# TP-34.net
KiCad netlist of a schematic drawn in EAGLE
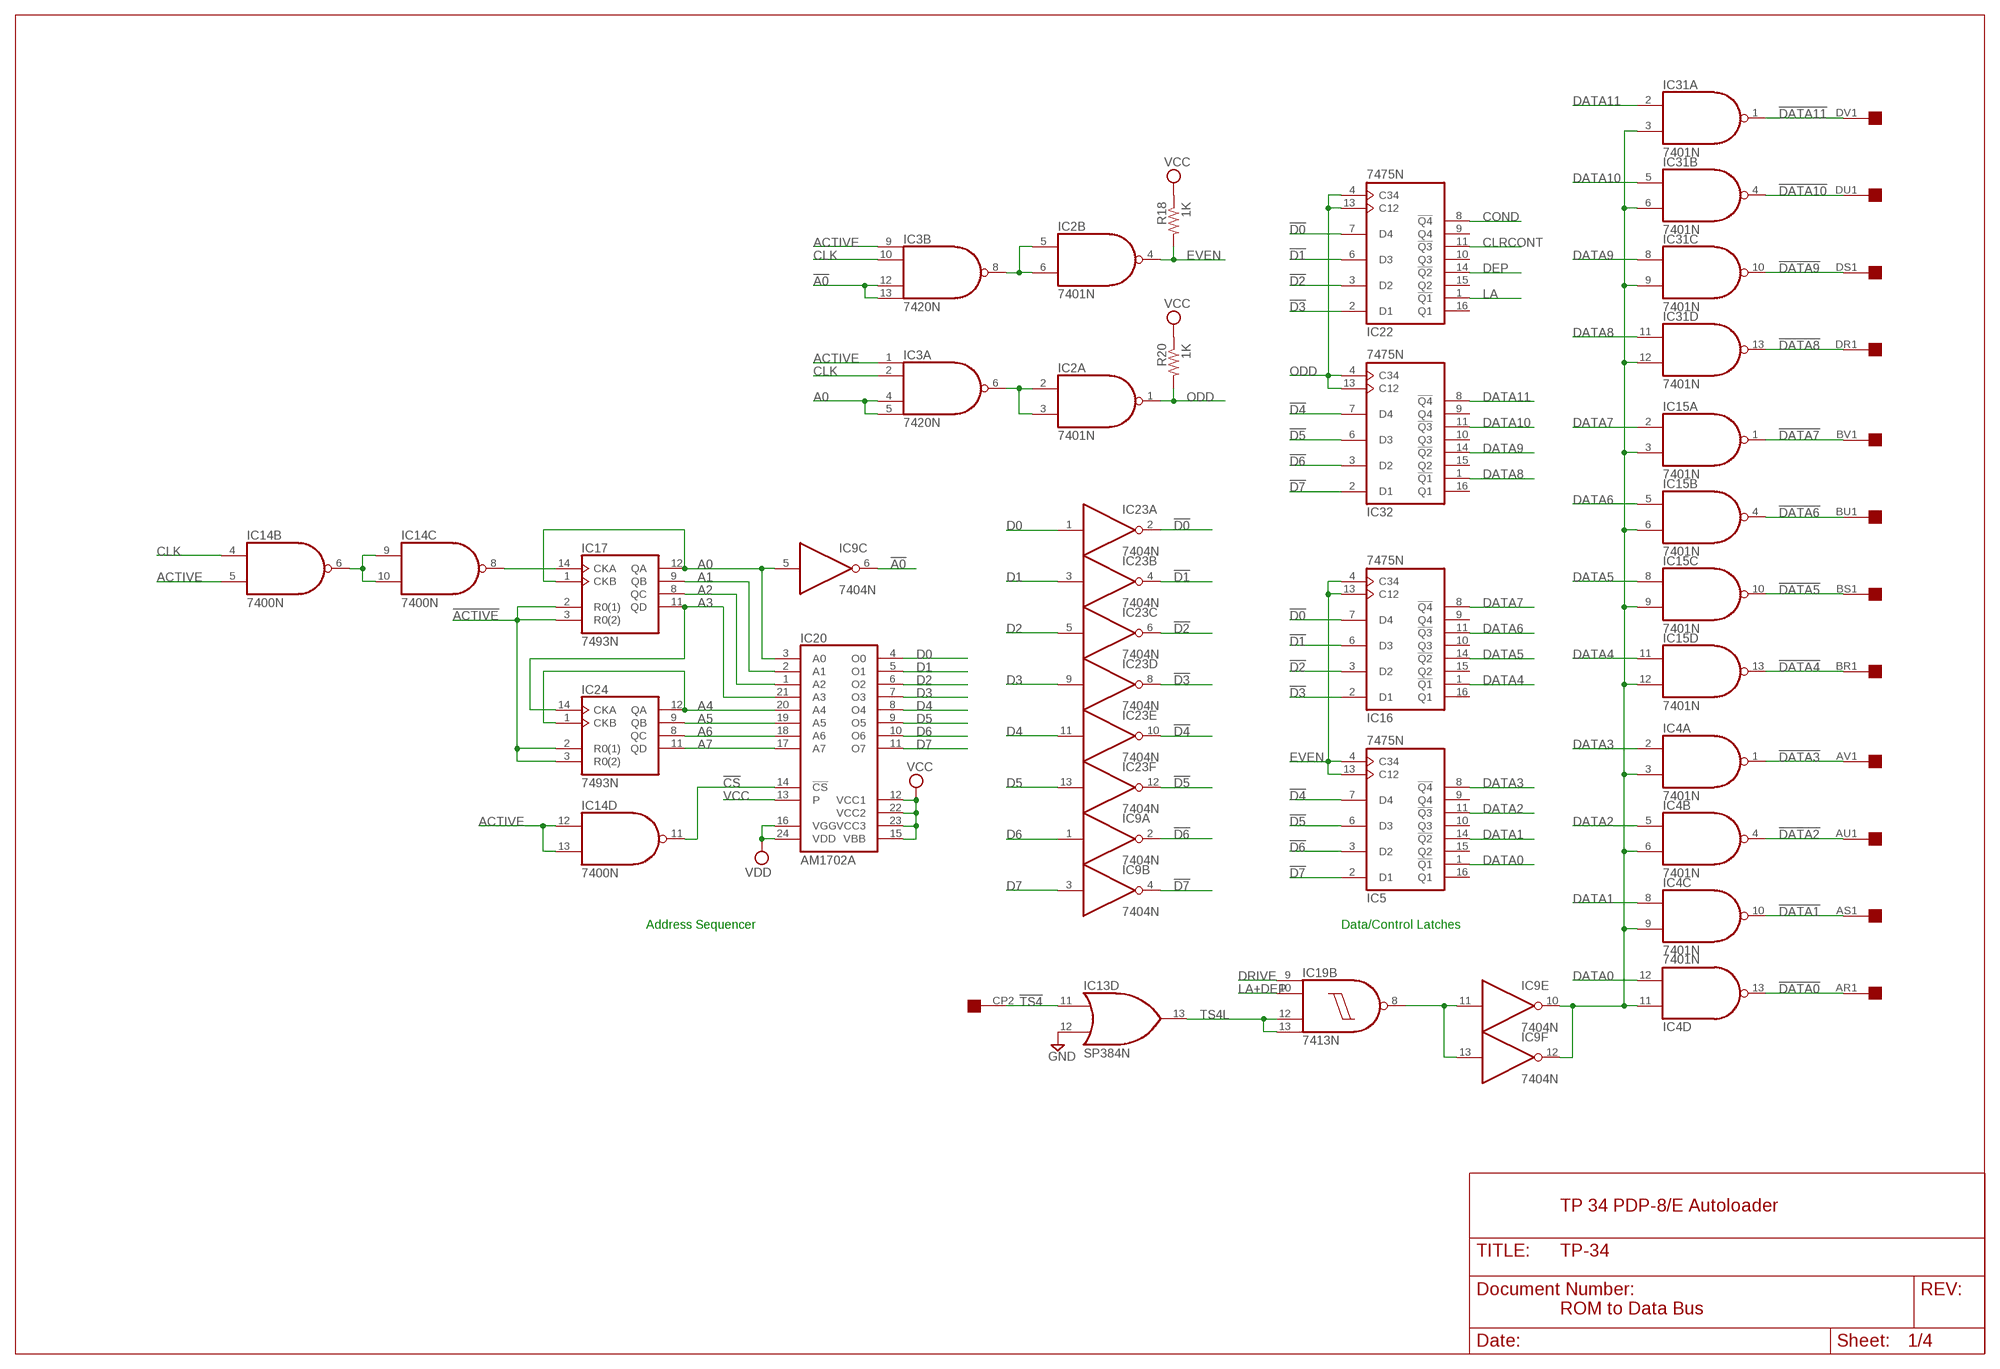
[diagram p0: schematic, sheet 1]
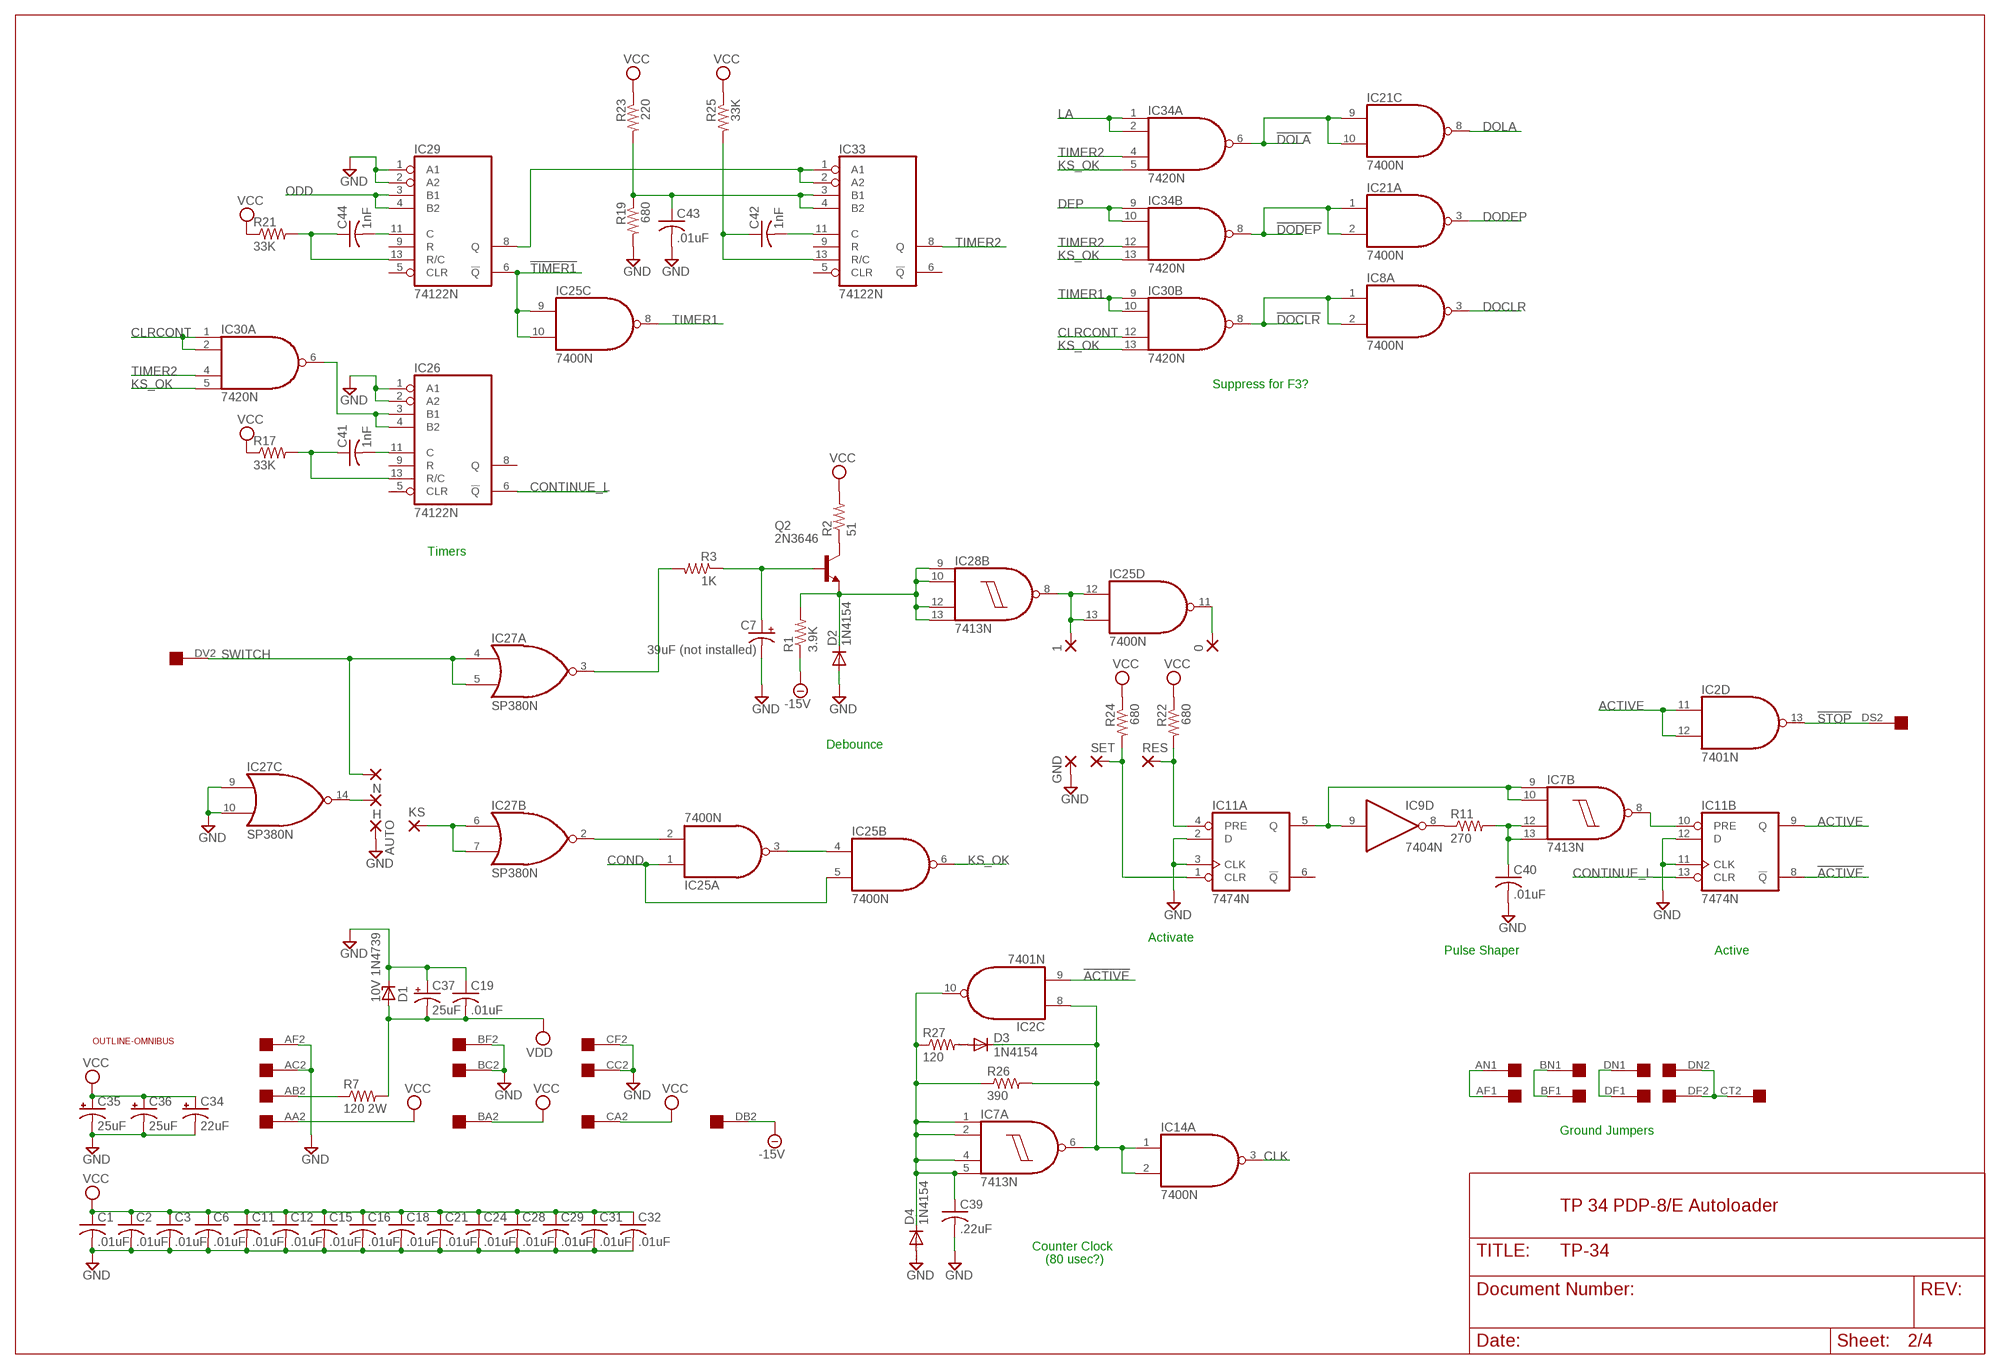
[diagram p1: schematic, sheet 2]
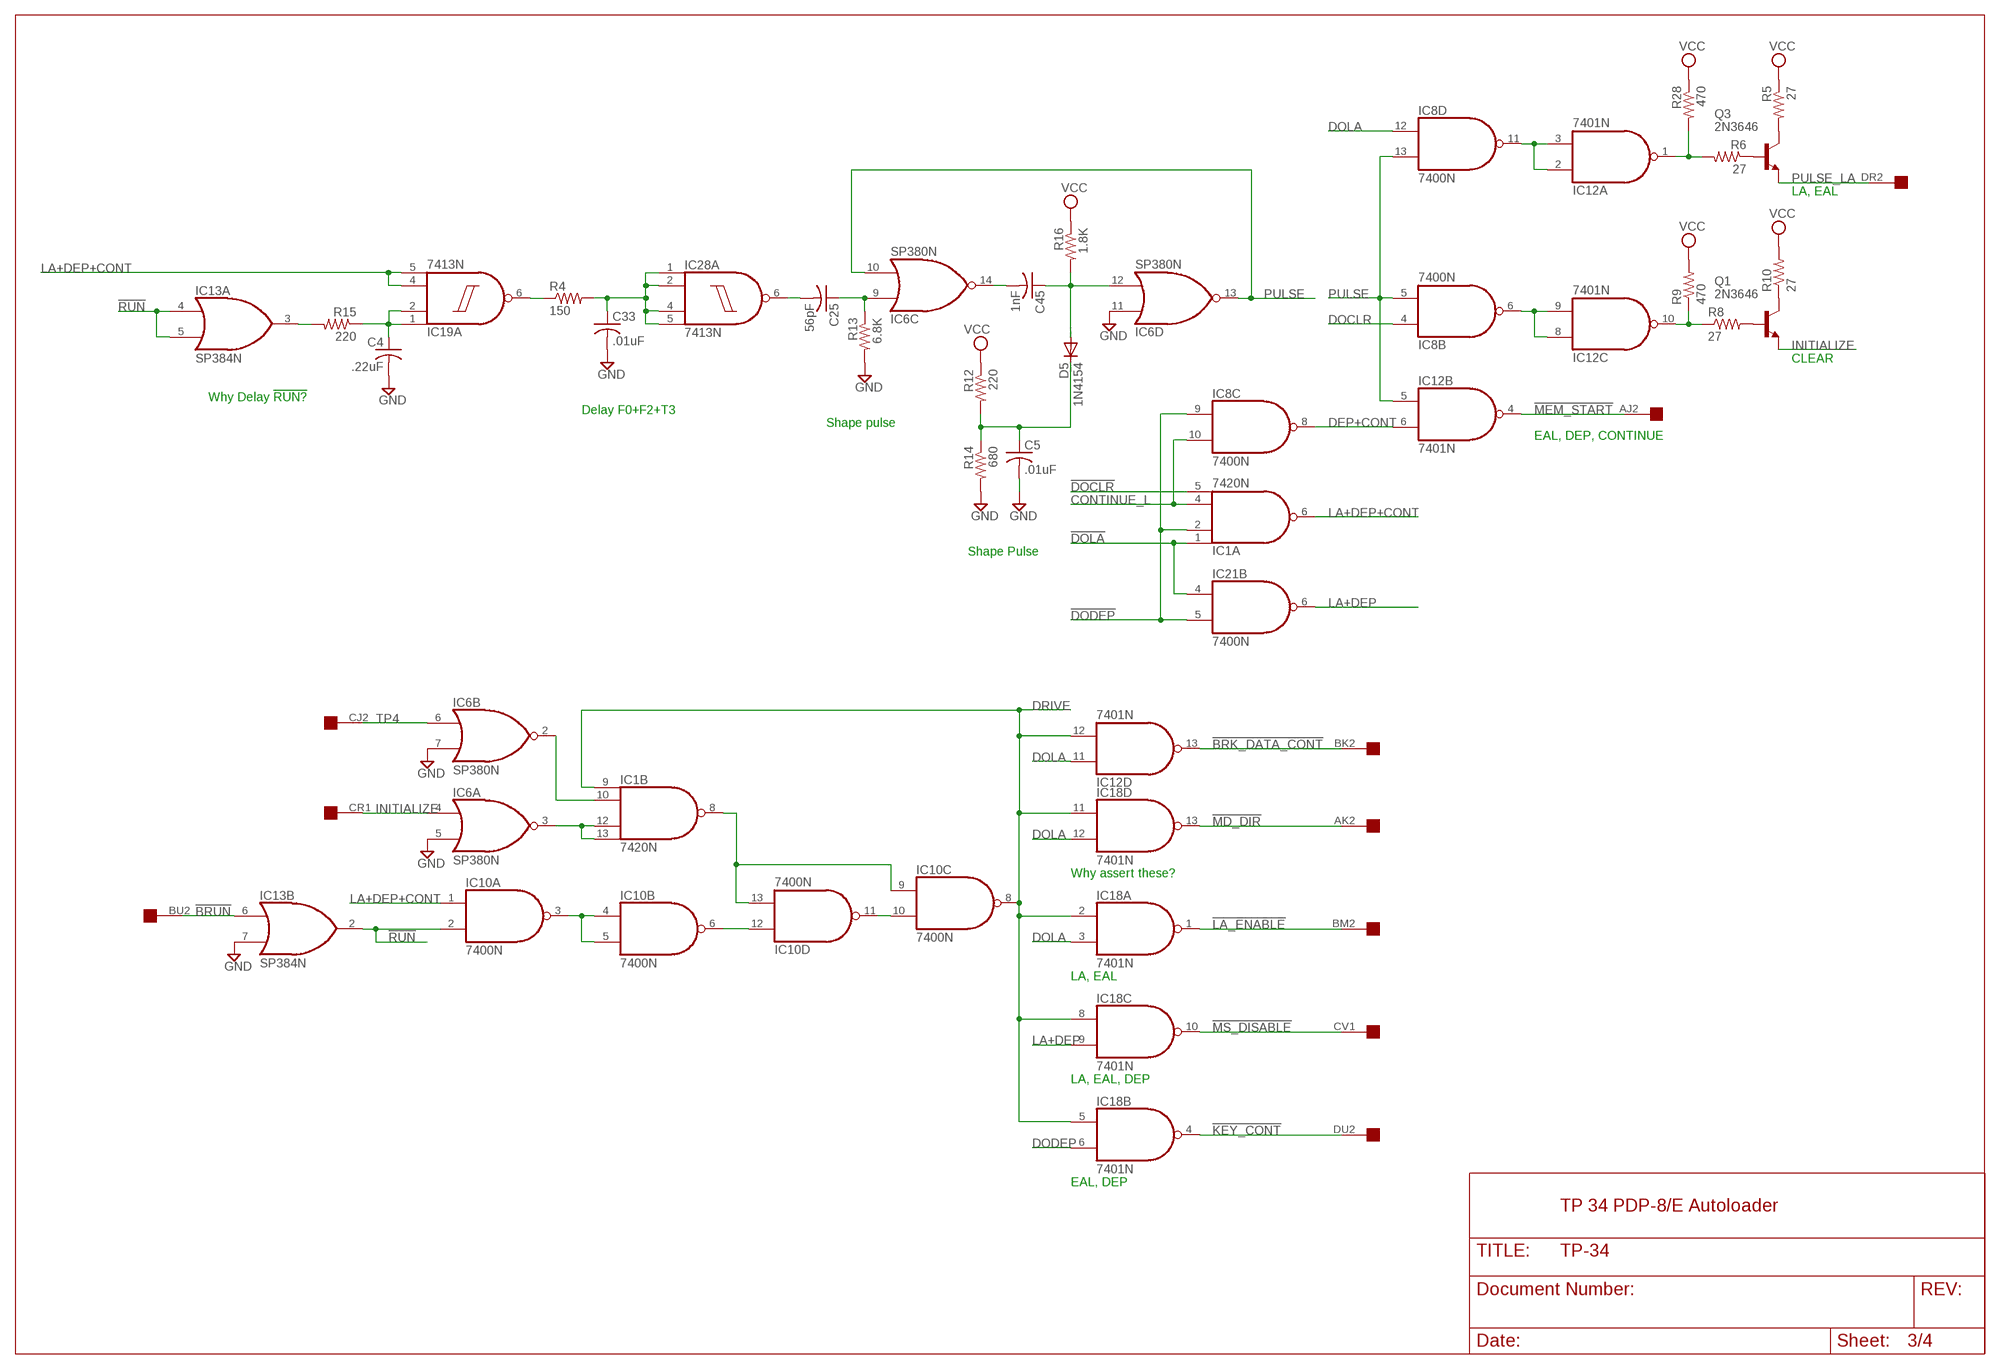
[diagram p2: schematic, sheet 3]
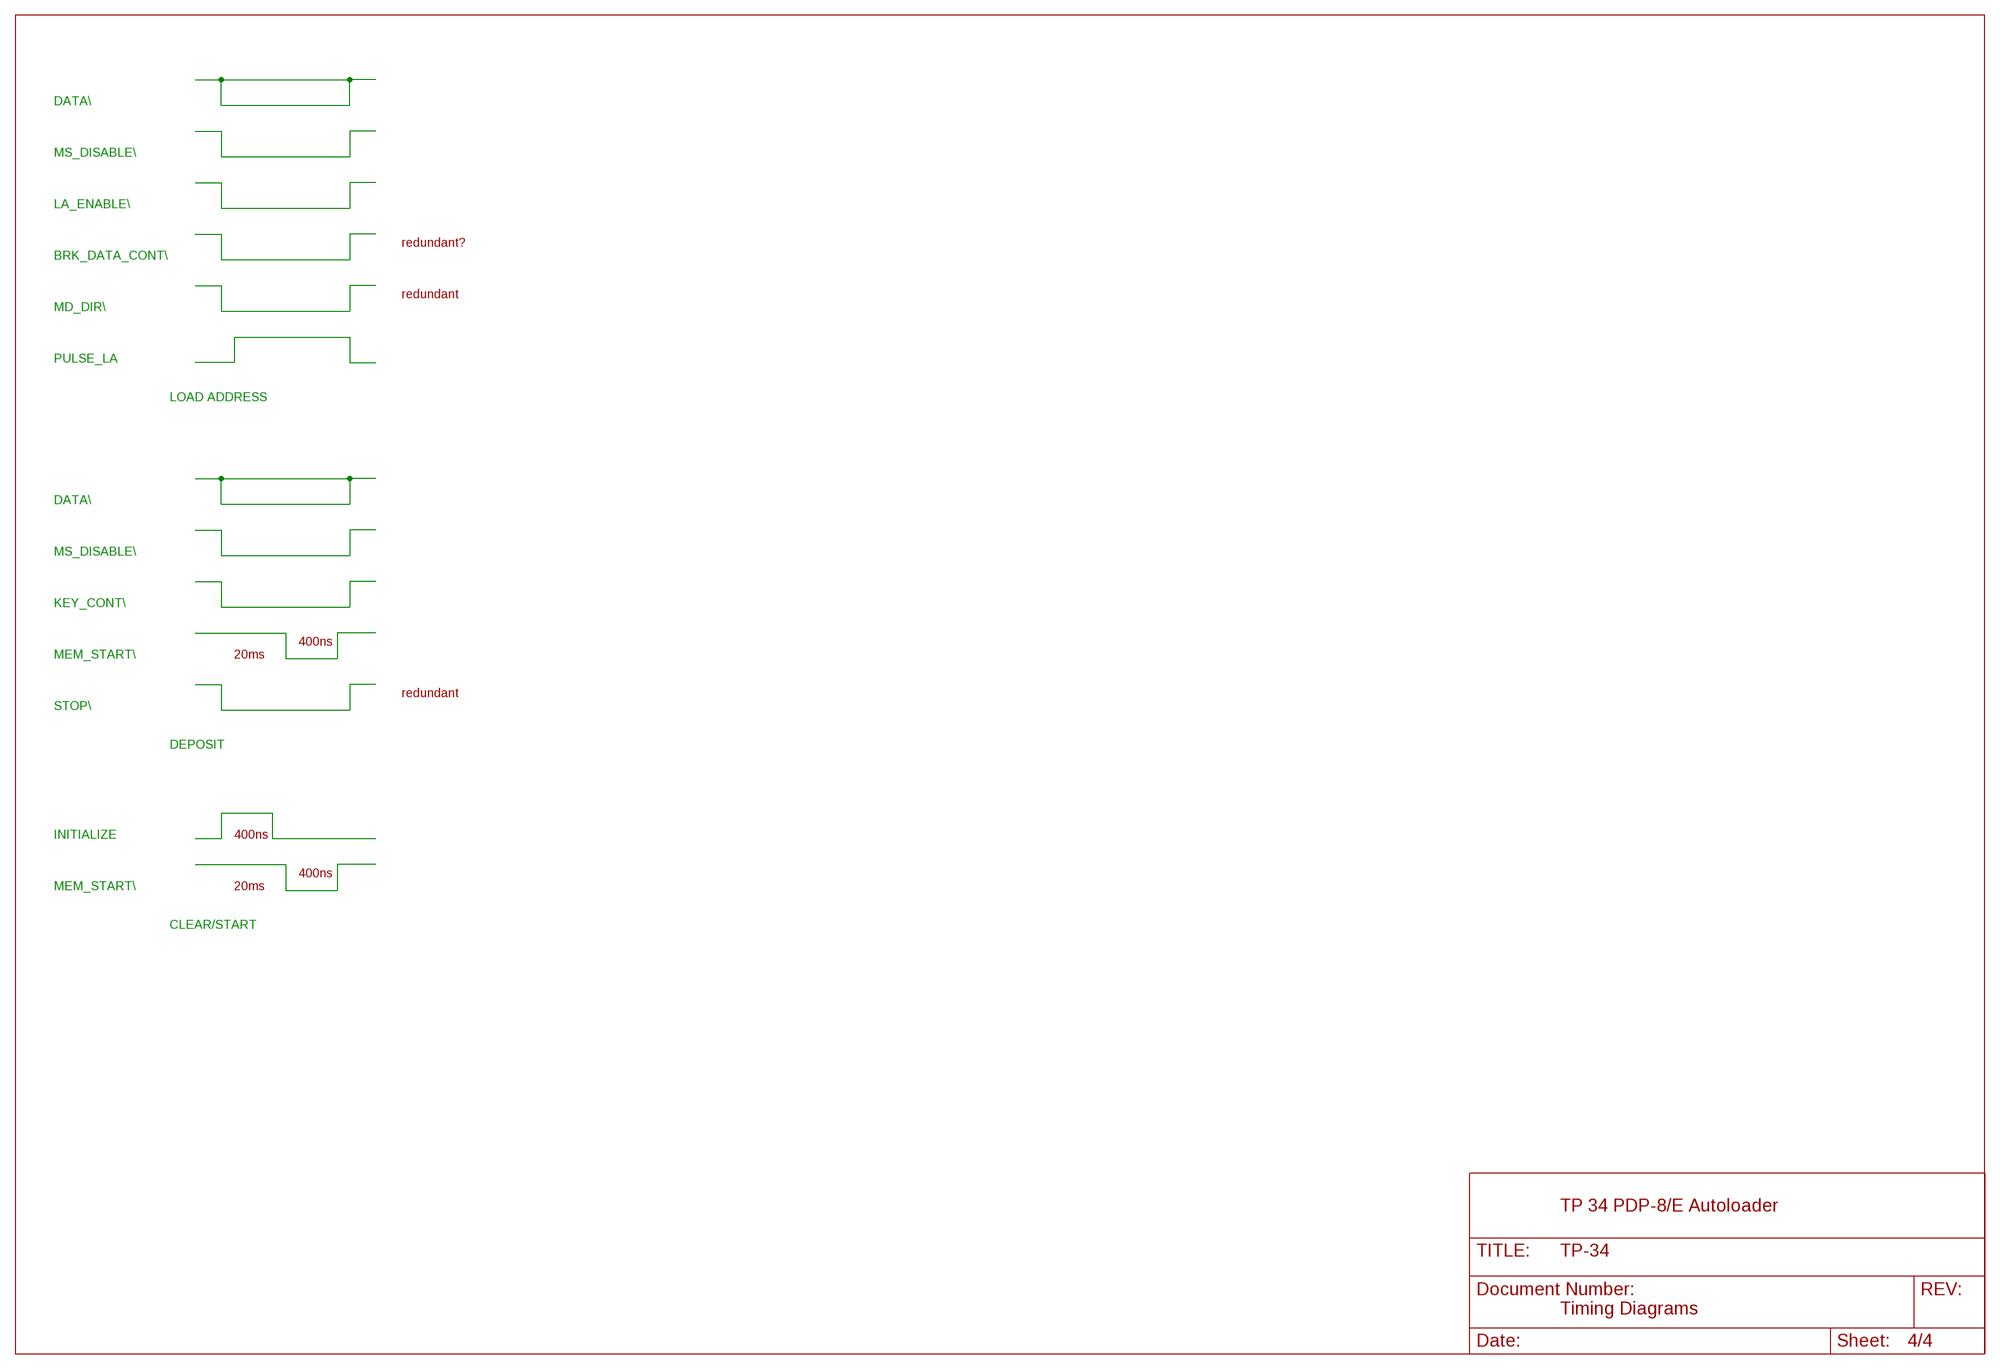
[diagram p3: schematic, sheet 4]

(export (version "E")
  (design (tool "Eeschema 10.0.6"))
  (components
    (comp (ref "0")
      (value "1,6/0,8")
      (footprint "eagle-import:1,6_0,8")
      (libsource (lib "eagle-import") (part "1,6/0,8"))
    )
    (comp (ref "1")
      (value "1,6/0,8")
      (footprint "eagle-import:1,6_0,8")
      (libsource (lib "eagle-import") (part "1,6/0,8"))
    )
    (comp (ref "AUTO")
      (value "1,6/0,8")
      (footprint "eagle-import:1,6_0,8")
      (libsource (lib "eagle-import") (part "1,6/0,8"))
    )
    (comp (ref "C1")
      (value ".01uF")
      (footprint "eagle-import:C075-032X103")
      (libsource (lib "eagle-import") (part "C-US075-032X103"))
    )
    (comp (ref "C2")
      (value ".01uF")
      (footprint "eagle-import:C075-032X103")
      (libsource (lib "eagle-import") (part "C-US075-032X103"))
    )
    (comp (ref "C3")
      (value ".01uF")
      (footprint "eagle-import:C075-032X103")
      (libsource (lib "eagle-import") (part "C-US075-032X103"))
    )
    (comp (ref "C6")
      (value ".01uF")
      (footprint "eagle-import:C075-032X103")
      (libsource (lib "eagle-import") (part "C-US075-032X103"))
    )
    (comp (ref "C7")
      (value "39uF (not installed)")
      (footprint "eagle-import:E15-5")
      (libsource (lib "eagle-import") (part "CPOL-USE15-5AXIAL"))
    )
    (comp (ref "C11")
      (value ".01uF")
      (footprint "eagle-import:C075-032X103")
      (libsource (lib "eagle-import") (part "C-US075-032X103"))
    )
    (comp (ref "C12")
      (value ".01uF")
      (footprint "eagle-import:C075-032X103")
      (libsource (lib "eagle-import") (part "C-US075-032X103"))
    )
    (comp (ref "C15")
      (value ".01uF")
      (footprint "eagle-import:C075-032X103")
      (libsource (lib "eagle-import") (part "C-US075-032X103"))
    )
    (comp (ref "C16")
      (value ".01uF")
      (footprint "eagle-import:C075-032X103")
      (libsource (lib "eagle-import") (part "C-US075-032X103"))
    )
    (comp (ref "C18")
      (value ".01uF")
      (footprint "eagle-import:C075-032X103")
      (libsource (lib "eagle-import") (part "C-US075-032X103"))
    )
    (comp (ref "C19")
      (value ".01uF")
      (footprint "eagle-import:C075-032X103")
      (libsource (lib "eagle-import") (part "C-US075-032X103"))
    )
    (comp (ref "C21")
      (value ".01uF")
      (footprint "eagle-import:C075-032X103")
      (libsource (lib "eagle-import") (part "C-US075-032X103"))
    )
    (comp (ref "C24")
      (value ".01uF")
      (footprint "eagle-import:C075-032X103")
      (libsource (lib "eagle-import") (part "C-US075-032X103"))
    )
    (comp (ref "C28")
      (value ".01uF")
      (footprint "eagle-import:C075-032X103")
      (libsource (lib "eagle-import") (part "C-US075-032X103"))
    )
    (comp (ref "C29")
      (value ".01uF")
      (footprint "eagle-import:C075-032X103")
      (libsource (lib "eagle-import") (part "C-US075-032X103"))
    )
    (comp (ref "C31")
      (value ".01uF")
      (footprint "eagle-import:C075-032X103")
      (libsource (lib "eagle-import") (part "C-US075-032X103"))
    )
    (comp (ref "C32")
      (value ".01uF")
      (footprint "eagle-import:C075-032X103")
      (libsource (lib "eagle-import") (part "C-US075-032X103"))
    )
    (comp (ref "C34")
      (value "22uF")
      (footprint "eagle-import:E12-8")
      (libsource (lib "eagle-import") (part "CPOL-USE20-8AXIAL"))
    )
    (comp (ref "C35")
      (value "25uF")
      (footprint "eagle-import:E15-5")
      (libsource (lib "eagle-import") (part "CPOL-USE15-5AXIAL"))
    )
    (comp (ref "C36")
      (value "25uF")
      (footprint "eagle-import:E15-5")
      (libsource (lib "eagle-import") (part "CPOL-USE15-5AXIAL"))
    )
    (comp (ref "C37")
      (value "25uF")
      (footprint "eagle-import:E15-5")
      (libsource (lib "eagle-import") (part "CPOL-USE15-5AXIAL"))
    )
    (comp (ref "C39")
      (value ".22uF")
      (footprint "eagle-import:C075-032X103")
      (libsource (lib "eagle-import") (part "C-US075-032X103"))
    )
    (comp (ref "C40")
      (value ".01uF")
      (footprint "eagle-import:C075-032X103")
      (libsource (lib "eagle-import") (part "C-US075-032X103"))
    )
    (comp (ref "C41")
      (value "1nF")
      (footprint "eagle-import:C075-032X103")
      (libsource (lib "eagle-import") (part "C-US075-032X103"))
    )
    (comp (ref "C42")
      (value "1nF")
      (footprint "eagle-import:C075-032X103")
      (libsource (lib "eagle-import") (part "C-US075-032X103"))
    )
    (comp (ref "C43")
      (value ".01uF")
      (footprint "eagle-import:C075-032X103")
      (libsource (lib "eagle-import") (part "C-US075-032X103"))
    )
    (comp (ref "C44")
      (value "1nF")
      (footprint "eagle-import:C075-032X103")
      (libsource (lib "eagle-import") (part "C-US075-032X103"))
    )
    (comp (ref "D1")
      (value "10V 1N4739")
      (footprint "eagle-import:C1702-15")
      (libsource (lib "eagle-import") (part "ZENER-DIODEC1702-15"))
    )
    (comp (ref "D2")
      (value "1N4154")
      (footprint "eagle-import:DO35-10")
      (libsource (lib "eagle-import") (part "1N4148DO35-10"))
    )
    (comp (ref "D3")
      (value "1N4154")
      (footprint "eagle-import:DO35-10")
      (libsource (lib "eagle-import") (part "1N4148DO35-10"))
    )
    (comp (ref "D4")
      (value "1N4154")
      (footprint "eagle-import:DO35-10")
      (libsource (lib "eagle-import") (part "1N4148DO35-10"))
    )
    (comp (ref "GND")
      (value "1,6/0,8")
      (footprint "eagle-import:1,6_0,8")
      (libsource (lib "eagle-import") (part "1,6/0,8"))
    )
    (comp (ref "H")
      (value "1,6/0,8")
      (footprint "eagle-import:1,6_0,8")
      (libsource (lib "eagle-import") (part "1,6/0,8"))
    )
    (comp (ref "IC2")
      (value "7401N")
      (footprint "eagle-import:DIL14")
      (libsource (lib "eagle-import") (part "7401NLS"))
    )
    (comp (ref "IC7")
      (value "7413N")
      (footprint "eagle-import:DIL14")
      (libsource (lib "eagle-import") (part "7413N"))
    )
    (comp (ref "IC8")
      (value "7400N")
      (footprint "eagle-import:DIL14")
      (libsource (lib "eagle-import") (part "7400N"))
    )
    (comp (ref "IC9")
      (value "7404N")
      (footprint "eagle-import:DIL14")
      (libsource (lib "eagle-import") (part "7404N"))
    )
    (comp (ref "IC11")
      (value "7474N")
      (footprint "eagle-import:DIL14")
      (libsource (lib "eagle-import") (part "7474NS"))
    )
    (comp (ref "IC14")
      (value "7400N")
      (footprint "eagle-import:DIL14")
      (libsource (lib "eagle-import") (part "7400N"))
    )
    (comp (ref "IC21")
      (value "7400N")
      (footprint "eagle-import:DIL14")
      (libsource (lib "eagle-import") (part "7400N"))
    )
    (comp (ref "IC25")
      (value "7400N")
      (footprint "eagle-import:DIL14")
      (libsource (lib "eagle-import") (part "7400N"))
    )
    (comp (ref "IC26")
      (value "74122N")
      (footprint "eagle-import:DIL14")
      (libsource (lib "eagle-import") (part "74122NLS"))
    )
    (comp (ref "IC27")
      (value "SP380N")
      (footprint "eagle-import:DIL14")
      (libsource (lib "eagle-import") (part "SP380N"))
    )
    (comp (ref "IC28")
      (value "7413N")
      (footprint "eagle-import:DIL14")
      (libsource (lib "eagle-import") (part "7413N"))
    )
    (comp (ref "IC29")
      (value "74122N")
      (footprint "eagle-import:DIL14")
      (libsource (lib "eagle-import") (part "74122NLS"))
    )
    (comp (ref "IC30")
      (value "7420N")
      (footprint "eagle-import:DIL14")
      (libsource (lib "eagle-import") (part "7420NS"))
    )
    (comp (ref "IC33")
      (value "74122N")
      (footprint "eagle-import:DIL14")
      (libsource (lib "eagle-import") (part "74122NLS"))
    )
    (comp (ref "IC34")
      (value "7420N")
      (footprint "eagle-import:DIL14")
      (libsource (lib "eagle-import") (part "7420NS"))
    )
    (comp (ref "KS")
      (value "1,6/0,8")
      (footprint "eagle-import:1,6_0,8")
      (libsource (lib "eagle-import") (part "1,6/0,8"))
    )
    (comp (ref "N")
      (value "1,6/0,8")
      (footprint "eagle-import:1,6_0,8")
      (libsource (lib "eagle-import") (part "1,6/0,8"))
    )
    (comp (ref "Q2")
      (value "2N3646")
      (footprint "eagle-import:TO5")
      (libsource (lib "eagle-import") (part "2N2102"))
    )
    (comp (ref "R1")
      (value "3.9K")
      (footprint "eagle-import:0207_10")
      (libsource (lib "eagle-import") (part "R-US_0207/10"))
    )
    (comp (ref "R2")
      (value "51")
      (footprint "eagle-import:0207_10")
      (libsource (lib "eagle-import") (part "R-US_0207/10"))
    )
    (comp (ref "R3")
      (value "1K")
      (footprint "eagle-import:0207_10")
      (libsource (lib "eagle-import") (part "R-US_0207/10"))
    )
    (comp (ref "R7")
      (value "120 2W")
      (footprint "eagle-import:0414_15")
      (libsource (lib "eagle-import") (part "R-US_0414/15"))
    )
    (comp (ref "R11")
      (value "270")
      (footprint "eagle-import:0207_12")
      (libsource (lib "eagle-import") (part "R-US_0207/12"))
    )
    (comp (ref "R17")
      (value "33K")
      (footprint "eagle-import:0207_10")
      (libsource (lib "eagle-import") (part "R-US_0207/10"))
    )
    (comp (ref "R19")
      (value "680")
      (footprint "eagle-import:0207_10")
      (libsource (lib "eagle-import") (part "R-US_0207/10"))
    )
    (comp (ref "R21")
      (value "33K")
      (footprint "eagle-import:0207_10")
      (libsource (lib "eagle-import") (part "R-US_0207/10"))
    )
    (comp (ref "R22")
      (value "680")
      (footprint "eagle-import:0207_10")
      (libsource (lib "eagle-import") (part "R-US_0207/10"))
    )
    (comp (ref "R23")
      (value "220")
      (footprint "eagle-import:0207_10")
      (libsource (lib "eagle-import") (part "R-US_0207/10"))
    )
    (comp (ref "R24")
      (value "680")
      (footprint "eagle-import:0207_10")
      (libsource (lib "eagle-import") (part "R-US_0207/10"))
    )
    (comp (ref "R25")
      (value "33K")
      (footprint "eagle-import:0207_10")
      (libsource (lib "eagle-import") (part "R-US_0207/10"))
    )
    (comp (ref "R26")
      (value "390")
      (footprint "eagle-import:0207_10")
      (libsource (lib "eagle-import") (part "R-US_0207/10"))
    )
    (comp (ref "R27")
      (value "120")
      (footprint "eagle-import:0207_10")
      (libsource (lib "eagle-import") (part "R-US_0207/10"))
    )
    (comp (ref "RES")
      (value "1,6/0,8")
      (footprint "eagle-import:1,6_0,8")
      (libsource (lib "eagle-import") (part "1,6/0,8"))
    )
    (comp (ref "SET")
      (value "1,6/0,8")
      (footprint "eagle-import:1,6_0,8")
      (libsource (lib "eagle-import") (part "1,6/0,8"))
    )
    (comp (ref "U$1")
      (value "OUTLINE-OMNIBUS")
      (footprint "eagle-import:OMNIBUS")
      (libsource (lib "eagle-import") (part "OUTLINE-OMNIBUS"))
    )
    (comp (ref "U$2")
      (value "QUAD")
      (footprint "eagle-import:EDGE-CON8")
      (libsource (lib "eagle-import") (part "QUAD"))
    )
    (comp (ref "C4")
      (value ".22uF")
      (footprint "eagle-import:C075-032X103")
      (libsource (lib "eagle-import") (part "C-US075-032X103"))
    )
    (comp (ref "C5")
      (value ".01uF")
      (footprint "eagle-import:C075-032X103")
      (libsource (lib "eagle-import") (part "C-US075-032X103"))
    )
    (comp (ref "C25")
      (value "56pF")
      (footprint "eagle-import:C102-043X133")
      (libsource (lib "eagle-import") (part "C-US102-043X133"))
    )
    (comp (ref "C33")
      (value ".01uF")
      (footprint "eagle-import:C075-032X103")
      (libsource (lib "eagle-import") (part "C-US075-032X103"))
    )
    (comp (ref "C45")
      (value "1nF")
      (footprint "eagle-import:C050-035X075")
      (libsource (lib "eagle-import") (part "C-US050-035X075"))
    )
    (comp (ref "D5")
      (value "1N4154")
      (footprint "eagle-import:DO35-10")
      (libsource (lib "eagle-import") (part "1N4148DO35-10"))
    )
    (comp (ref "IC1")
      (value "7420N")
      (footprint "eagle-import:DIL14")
      (libsource (lib "eagle-import") (part "7420NS"))
    )
    (comp (ref "IC6")
      (value "SP380N")
      (footprint "eagle-import:DIL14")
      (libsource (lib "eagle-import") (part "SP380N"))
    )
    (comp (ref "IC10")
      (value "7400N")
      (footprint "eagle-import:DIL14")
      (libsource (lib "eagle-import") (part "7400N"))
    )
    (comp (ref "IC12")
      (value "7401N")
      (footprint "eagle-import:DIL14")
      (libsource (lib "eagle-import") (part "7401NLS"))
    )
    (comp (ref "IC13")
      (value "SP384N")
      (footprint "eagle-import:DIL14")
      (libsource (lib "eagle-import") (part "SP384N"))
    )
    (comp (ref "IC18")
      (value "7401N")
      (footprint "eagle-import:DIL14")
      (libsource (lib "eagle-import") (part "7401NLS"))
    )
    (comp (ref "IC19")
      (value "7413N")
      (footprint "eagle-import:DIL14")
      (libsource (lib "eagle-import") (part "7413N"))
    )
    (comp (ref "Q1")
      (value "2N3646")
      (footprint "eagle-import:TO5")
      (libsource (lib "eagle-import") (part "2N2102"))
    )
    (comp (ref "Q3")
      (value "2N3646")
      (footprint "eagle-import:TO5")
      (libsource (lib "eagle-import") (part "2N2102"))
    )
    (comp (ref "R4")
      (value "150")
      (footprint "eagle-import:0207_10")
      (libsource (lib "eagle-import") (part "R-US_0207/10"))
    )
    (comp (ref "R5")
      (value "27")
      (footprint "eagle-import:0207_10")
      (libsource (lib "eagle-import") (part "R-US_0207/10"))
    )
    (comp (ref "R6")
      (value "27")
      (footprint "eagle-import:0207_10")
      (libsource (lib "eagle-import") (part "R-US_0207/10"))
    )
    (comp (ref "R8")
      (value "27")
      (footprint "eagle-import:0207_10")
      (libsource (lib "eagle-import") (part "R-US_0207/10"))
    )
    (comp (ref "R9")
      (value "470")
      (footprint "eagle-import:0207_10")
      (libsource (lib "eagle-import") (part "R-US_0207/10"))
    )
    (comp (ref "R10")
      (value "27")
      (footprint "eagle-import:0207_10")
      (libsource (lib "eagle-import") (part "R-US_0207/10"))
    )
    (comp (ref "R12")
      (value "220")
      (footprint "eagle-import:0207_10")
      (libsource (lib "eagle-import") (part "R-US_0207/10"))
    )
    (comp (ref "R13")
      (value "6.8K")
      (footprint "eagle-import:0207_10")
      (libsource (lib "eagle-import") (part "R-US_0207/10"))
    )
    (comp (ref "R14")
      (value "680")
      (footprint "eagle-import:0207_10")
      (libsource (lib "eagle-import") (part "R-US_0207/10"))
    )
    (comp (ref "R15")
      (value "220")
      (footprint "eagle-import:0207_15")
      (libsource (lib "eagle-import") (part "R-US_0207/15"))
    )
    (comp (ref "R16")
      (value "1.8K")
      (footprint "eagle-import:0207_10")
      (libsource (lib "eagle-import") (part "R-US_0207/10"))
    )
    (comp (ref "R28")
      (value "470")
      (footprint "eagle-import:0207_10")
      (libsource (lib "eagle-import") (part "R-US_0207/10"))
    )
    (comp (ref "IC3")
      (value "7420N")
      (footprint "eagle-import:DIL14")
      (libsource (lib "eagle-import") (part "7420NS"))
    )
    (comp (ref "IC4")
      (value "7401N")
      (footprint "eagle-import:DIL14")
      (libsource (lib "eagle-import") (part "7401NLS"))
    )
    (comp (ref "IC5")
      (value "7475N")
      (footprint "eagle-import:DIL16")
      (libsource (lib "eagle-import") (part "7475N"))
    )
    (comp (ref "IC15")
      (value "7401N")
      (footprint "eagle-import:DIL14")
      (libsource (lib "eagle-import") (part "7401NLS"))
    )
    (comp (ref "IC16")
      (value "7475N")
      (footprint "eagle-import:DIL16")
      (libsource (lib "eagle-import") (part "7475N"))
    )
    (comp (ref "IC17")
      (value "7493N")
      (footprint "eagle-import:DIL14")
      (libsource (lib "eagle-import") (part "7493NLS"))
    )
    (comp (ref "IC20")
      (value "AM1702A")
      (footprint "eagle-import:DIL24")
      (libsource (lib "eagle-import") (part "AM1702"))
    )
    (comp (ref "IC22")
      (value "7475N")
      (footprint "eagle-import:DIL16")
      (libsource (lib "eagle-import") (part "7475N"))
    )
    (comp (ref "IC23")
      (value "7404N")
      (footprint "eagle-import:DIL14")
      (libsource (lib "eagle-import") (part "7404N"))
    )
    (comp (ref "IC24")
      (value "7493N")
      (footprint "eagle-import:DIL14")
      (libsource (lib "eagle-import") (part "7493NLS"))
    )
    (comp (ref "IC31")
      (value "7401N")
      (footprint "eagle-import:DIL14")
      (libsource (lib "eagle-import") (part "7401NLS"))
    )
    (comp (ref "IC32")
      (value "7475N")
      (footprint "eagle-import:DIL16")
      (libsource (lib "eagle-import") (part "7475N"))
    )
    (comp (ref "R18")
      (value "1K")
      (footprint "eagle-import:0207_10")
      (libsource (lib "eagle-import") (part "R-US_0207/10"))
    )
    (comp (ref "R20")
      (value "1K")
      (footprint "eagle-import:0207_10")
      (libsource (lib "eagle-import") (part "R-US_0207/10"))
    )
  )
  (nets
    (net (code "1") (name "-15V") (class "Default")
      (node (ref "R1") (pin "1") (pinfunction "1_1") (pintype "passive"))
      (node (ref "U$2") (pin "DB2") (pinfunction "1_DB2") (pintype "bidirectional"))
    )
    (net (code "2") (name "A0") (class "Default")
      (node (ref "IC17") (pin "1") (pinfunction "CKB_1") (pintype "input"))
      (node (ref "IC17") (pin "12") (pinfunction "QA_12") (pintype "output"))
      (node (ref "IC20") (pin "3") (pinfunction "A0_3") (pintype "input"))
      (node (ref "IC3") (pin "4") (pinfunction "I2_4") (pintype "input"))
      (node (ref "IC3") (pin "5") (pinfunction "I3_5") (pintype "input"))
      (node (ref "IC9") (pin "5") (pinfunction "I_5") (pintype "input"))
    )
    (net (code "3") (name "A1") (class "Default")
      (node (ref "IC17") (pin "9") (pinfunction "QB_9") (pintype "output"))
      (node (ref "IC20") (pin "2") (pinfunction "A1_2") (pintype "input"))
    )
    (net (code "4") (name "A2") (class "Default")
      (node (ref "IC17") (pin "8") (pinfunction "QC_8") (pintype "output"))
      (node (ref "IC20") (pin "1") (pinfunction "A2_1") (pintype "input"))
    )
    (net (code "5") (name "A3") (class "Default")
      (node (ref "IC17") (pin "11") (pinfunction "QD_11") (pintype "output"))
      (node (ref "IC20") (pin "21") (pinfunction "A3_21") (pintype "input"))
      (node (ref "IC24") (pin "14") (pinfunction "CKA_14") (pintype "input"))
    )
    (net (code "6") (name "A4") (class "Default")
      (node (ref "IC20") (pin "20") (pinfunction "A4_20") (pintype "input"))
      (node (ref "IC24") (pin "1") (pinfunction "CKB_1") (pintype "input"))
      (node (ref "IC24") (pin "12") (pinfunction "QA_12") (pintype "output"))
    )
    (net (code "7") (name "A5") (class "Default")
      (node (ref "IC20") (pin "19") (pinfunction "A5_19") (pintype "input"))
      (node (ref "IC24") (pin "9") (pinfunction "QB_9") (pintype "output"))
    )
    (net (code "8") (name "A6") (class "Default")
      (node (ref "IC20") (pin "18") (pinfunction "A6_18") (pintype "input"))
      (node (ref "IC24") (pin "8") (pinfunction "QC_8") (pintype "output"))
    )
    (net (code "9") (name "A7") (class "Default")
      (node (ref "IC20") (pin "17") (pinfunction "A7_17") (pintype "input"))
      (node (ref "IC24") (pin "11") (pinfunction "QD_11") (pintype "output"))
    )
    (net (code "10") (name "ACTIVE") (class "Default")
      (node (ref "IC11") (pin "9") (pinfunction "Q_9") (pintype "output"))
      (node (ref "IC14") (pin "12") (pinfunction "I0_12") (pintype "input"))
      (node (ref "IC14") (pin "13") (pinfunction "I1_13") (pintype "input"))
      (node (ref "IC14") (pin "5") (pinfunction "I1_5") (pintype "input"))
      (node (ref "IC2") (pin "11") (pinfunction "I0_11") (pintype "input"))
      (node (ref "IC2") (pin "12") (pinfunction "I1_12") (pintype "input"))
      (node (ref "IC3") (pin "1") (pinfunction "I0_1") (pintype "input"))
      (node (ref "IC3") (pin "9") (pinfunction "I0_9") (pintype "input"))
    )
    (net (code "11") (name "CLK") (class "Default")
      (node (ref "IC14") (pin "3") (pinfunction "O_3") (pintype "output"))
      (node (ref "IC14") (pin "4") (pinfunction "I0_4") (pintype "input"))
      (node (ref "IC3") (pin "10") (pinfunction "I1_10") (pintype "input"))
      (node (ref "IC3") (pin "2") (pinfunction "I1_2") (pintype "input"))
    )
    (net (code "12") (name "CLRCONT") (class "Default")
      (node (ref "IC22") (pin "11") (pinfunction "~{Q3}_11") (pintype "output"))
      (node (ref "IC30") (pin "1") (pinfunction "I0_1") (pintype "input"))
      (node (ref "IC30") (pin "12") (pinfunction "I2_12") (pintype "input"))
      (node (ref "IC30") (pin "2") (pinfunction "I1_2") (pintype "input"))
    )
    (net (code "13") (name "COND") (class "Default")
      (node (ref "IC22") (pin "8") (pinfunction "~{Q4}_8") (pintype "output"))
      (node (ref "IC25") (pin "1") (pinfunction "I0_1") (pintype "input"))
      (node (ref "IC25") (pin "5") (pinfunction "I1_5") (pintype "input"))
    )
    (net (code "14") (name "CONTINUE_L") (class "Default")
      (node (ref "IC1") (pin "4") (pinfunction "I2_4") (pintype "input"))
      (node (ref "IC11") (pin "13") (pinfunction "CLR_13") (pintype "input"))
      (node (ref "IC26") (pin "6") (pinfunction "~{Q}_6") (pintype "output"))
      (node (ref "IC8") (pin "10") (pinfunction "I1_10") (pintype "input"))
    )
    (net (code "15") (name "D0") (class "Default")
      (node (ref "IC20") (pin "4") (pinfunction "O0_4") (pintype "tri_state"))
      (node (ref "IC23") (pin "1") (pinfunction "I_1") (pintype "input"))
    )
    (net (code "16") (name "D1") (class "Default")
      (node (ref "IC20") (pin "5") (pinfunction "O1_5") (pintype "tri_state"))
      (node (ref "IC23") (pin "3") (pinfunction "I_3") (pintype "input"))
    )
    (net (code "17") (name "D2") (class "Default")
      (node (ref "IC20") (pin "6") (pinfunction "O2_6") (pintype "tri_state"))
      (node (ref "IC23") (pin "5") (pinfunction "I_5") (pintype "input"))
    )
    (net (code "18") (name "D3") (class "Default")
      (node (ref "IC20") (pin "7") (pinfunction "O3_7") (pintype "tri_state"))
      (node (ref "IC23") (pin "9") (pinfunction "I_9") (pintype "input"))
    )
    (net (code "19") (name "D4") (class "Default")
      (node (ref "IC20") (pin "8") (pinfunction "O4_8") (pintype "tri_state"))
      (node (ref "IC23") (pin "11") (pinfunction "I_11") (pintype "input"))
    )
    (net (code "20") (name "D5") (class "Default")
      (node (ref "IC20") (pin "9") (pinfunction "O5_9") (pintype "tri_state"))
      (node (ref "IC23") (pin "13") (pinfunction "I_13") (pintype "input"))
    )
    (net (code "21") (name "D6") (class "Default")
      (node (ref "IC20") (pin "10") (pinfunction "O6_10") (pintype "tri_state"))
      (node (ref "IC9") (pin "1") (pinfunction "I_1") (pintype "input"))
    )
    (net (code "22") (name "D7") (class "Default")
      (node (ref "IC20") (pin "11") (pinfunction "O7_11") (pintype "tri_state"))
      (node (ref "IC9") (pin "3") (pinfunction "I_3") (pintype "input"))
    )
    (net (code "23") (name "DATA0") (class "Default")
      (node (ref "IC4") (pin "12") (pinfunction "I1_12") (pintype "input"))
      (node (ref "IC5") (pin "1") (pinfunction "~{Q1}_1") (pintype "output"))
    )
    (net (code "24") (name "DATA1") (class "Default")
      (node (ref "IC4") (pin "8") (pinfunction "I0_8") (pintype "input"))
      (node (ref "IC5") (pin "14") (pinfunction "~{Q2}_14") (pintype "output"))
    )
    (net (code "25") (name "DATA2") (class "Default")
      (node (ref "IC4") (pin "5") (pinfunction "I0_5") (pintype "input"))
      (node (ref "IC5") (pin "11") (pinfunction "~{Q3}_11") (pintype "output"))
    )
    (net (code "26") (name "DATA3") (class "Default")
      (node (ref "IC4") (pin "2") (pinfunction "I0_2") (pintype "input"))
      (node (ref "IC5") (pin "8") (pinfunction "~{Q4}_8") (pintype "output"))
    )
    (net (code "27") (name "DATA4") (class "Default")
      (node (ref "IC15") (pin "11") (pinfunction "I0_11") (pintype "input"))
      (node (ref "IC16") (pin "1") (pinfunction "~{Q1}_1") (pintype "output"))
    )
    (net (code "28") (name "DATA5") (class "Default")
      (node (ref "IC15") (pin "8") (pinfunction "I0_8") (pintype "input"))
      (node (ref "IC16") (pin "14") (pinfunction "~{Q2}_14") (pintype "output"))
    )
    (net (code "29") (name "DATA6") (class "Default")
      (node (ref "IC15") (pin "5") (pinfunction "I0_5") (pintype "input"))
      (node (ref "IC16") (pin "11") (pinfunction "~{Q3}_11") (pintype "output"))
    )
    (net (code "30") (name "DATA7") (class "Default")
      (node (ref "IC15") (pin "2") (pinfunction "I0_2") (pintype "input"))
      (node (ref "IC16") (pin "8") (pinfunction "~{Q4}_8") (pintype "output"))
    )
    (net (code "31") (name "DATA8") (class "Default")
      (node (ref "IC31") (pin "11") (pinfunction "I0_11") (pintype "input"))
      (node (ref "IC32") (pin "1") (pinfunction "~{Q1}_1") (pintype "output"))
    )
    (net (code "32") (name "DATA9") (class "Default")
      (node (ref "IC31") (pin "8") (pinfunction "I0_8") (pintype "input"))
      (node (ref "IC32") (pin "14") (pinfunction "~{Q2}_14") (pintype "output"))
    )
    (net (code "33") (name "DATA10") (class "Default")
      (node (ref "IC31") (pin "5") (pinfunction "I0_5") (pintype "input"))
      (node (ref "IC32") (pin "11") (pinfunction "~{Q3}_11") (pintype "output"))
    )
    (net (code "34") (name "DATA11") (class "Default")
      (node (ref "IC31") (pin "2") (pinfunction "I0_2") (pintype "input"))
      (node (ref "IC32") (pin "8") (pinfunction "~{Q4}_8") (pintype "output"))
    )
    (net (code "35") (name "DEP") (class "Default")
      (node (ref "IC22") (pin "14") (pinfunction "~{Q2}_14") (pintype "output"))
      (node (ref "IC34") (pin "10") (pinfunction "I1_10") (pintype "input"))
      (node (ref "IC34") (pin "9") (pinfunction "I0_9") (pintype "input"))
    )
    (net (code "36") (name "DEP+CONT") (class "Default")
      (node (ref "IC12") (pin "6") (pinfunction "I1_6") (pintype "input"))
      (node (ref "IC8") (pin "8") (pinfunction "O_8") (pintype "output"))
    )
    (net (code "37") (name "DOCLR") (class "Default")
      (node (ref "IC8") (pin "3") (pinfunction "O_3") (pintype "output"))
      (node (ref "IC8") (pin "4") (pinfunction "I0_4") (pintype "input"))
    )
    (net (code "38") (name "DODEP") (class "Default")
      (node (ref "IC18") (pin "6") (pinfunction "I1_6") (pintype "input"))
      (node (ref "IC21") (pin "3") (pinfunction "O_3") (pintype "output"))
    )
    (net (code "39") (name "DOLA") (class "Default")
      (node (ref "IC12") (pin "11") (pinfunction "I0_11") (pintype "input"))
      (node (ref "IC18") (pin "12") (pinfunction "I1_12") (pintype "input"))
      (node (ref "IC18") (pin "3") (pinfunction "I1_3") (pintype "input"))
      (node (ref "IC21") (pin "8") (pinfunction "O_8") (pintype "output"))
      (node (ref "IC8") (pin "12") (pinfunction "I0_12") (pintype "input"))
    )
    (net (code "40") (name "DRIVE") (class "Default")
      (node (ref "IC1") (pin "9") (pinfunction "I0_9") (pintype "input"))
      (node (ref "IC10") (pin "8") (pinfunction "O_8") (pintype "output"))
      (node (ref "IC12") (pin "12") (pinfunction "I1_12") (pintype "input"))
      (node (ref "IC18") (pin "11") (pinfunction "I0_11") (pintype "input"))
      (node (ref "IC18") (pin "2") (pinfunction "I0_2") (pintype "input"))
      (node (ref "IC18") (pin "5") (pinfunction "I0_5") (pintype "input"))
      (node (ref "IC18") (pin "8") (pinfunction "I0_8") (pintype "input"))
      (node (ref "IC19") (pin "9") (pinfunction "I0_9") (pintype "input"))
    )
    (net (code "41") (name "EVEN") (class "Default")
      (node (ref "IC16") (pin "13") (pinfunction "C12_13") (pintype "input"))
      (node (ref "IC16") (pin "4") (pinfunction "C34_4") (pintype "input"))
      (node (ref "IC2") (pin "4") (pinfunction "O_4") (pintype "open_collector"))
      (node (ref "IC5") (pin "13") (pinfunction "C12_13") (pintype "input"))
      (node (ref "IC5") (pin "4") (pinfunction "C34_4") (pintype "input"))
      (node (ref "R18") (pin "2") (pinfunction "2_2") (pintype "passive"))
    )
    (net (code "42") (name "GND") (class "Default")
      (node (ref "AUTO") (pin "1") (pinfunction "P_1") (pintype "passive"))
      (node (ref "C1") (pin "2") (pinfunction "2_2") (pintype "passive"))
      (node (ref "C11") (pin "2") (pinfunction "2_2") (pintype "passive"))
      (node (ref "C12") (pin "2") (pinfunction "2_2") (pintype "passive"))
      (node (ref "C15") (pin "2") (pinfunction "2_2") (pintype "passive"))
      (node (ref "C16") (pin "2") (pinfunction "2_2") (pintype "passive"))
      (node (ref "C18") (pin "2") (pinfunction "2_2") (pintype "passive"))
      (node (ref "C19") (pin "1") (pinfunction "1_1") (pintype "passive"))
      (node (ref "C2") (pin "2") (pinfunction "2_2") (pintype "passive"))
      (node (ref "C21") (pin "2") (pinfunction "2_2") (pintype "passive"))
      (node (ref "C24") (pin "2") (pinfunction "2_2") (pintype "passive"))
      (node (ref "C28") (pin "2") (pinfunction "2_2") (pintype "passive"))
      (node (ref "C29") (pin "2") (pinfunction "2_2") (pintype "passive"))
      (node (ref "C3") (pin "2") (pinfunction "2_2") (pintype "passive"))
      (node (ref "C31") (pin "2") (pinfunction "2_2") (pintype "passive"))
      (node (ref "C32") (pin "2") (pinfunction "2_2") (pintype "passive"))
      (node (ref "C33") (pin "2") (pinfunction "2_2") (pintype "passive"))
      (node (ref "C34") (pin "-") (pinfunction "-_-") (pintype "passive"))
      (node (ref "C35") (pin "-") (pinfunction "-_-") (pintype "passive"))
      (node (ref "C36") (pin "-") (pinfunction "-_-") (pintype "passive"))
      (node (ref "C37") (pin "+") (pinfunction "+_+") (pintype "passive"))
      (node (ref "C39") (pin "2") (pinfunction "2_2") (pintype "passive"))
      (node (ref "C4") (pin "2") (pinfunction "2_2") (pintype "passive"))
      (node (ref "C40") (pin "2") (pinfunction "2_2") (pintype "passive"))
      (node (ref "C43") (pin "2") (pinfunction "2_2") (pintype "passive"))
      (node (ref "C5") (pin "2") (pinfunction "2_2") (pintype "passive"))
      (node (ref "C6") (pin "2") (pinfunction "2_2") (pintype "passive"))
      (node (ref "C7") (pin "-") (pinfunction "-_-") (pintype "passive"))
      (node (ref "D1") (pin "C") (pinfunction "C_C") (pintype "passive"))
      (node (ref "D2") (pin "A") (pinfunction "A_A") (pintype "passive"))
      (node (ref "D4") (pin "A") (pinfunction "A_A") (pintype "passive"))
      (node (ref "GND") (pin "1") (pinfunction "P_1") (pintype "passive"))
      (node (ref "IC11") (pin "11") (pinfunction "CLK_11") (pintype "input"))
      (node (ref "IC11") (pin "12") (pinfunction "D_12") (pintype "input"))
      (node (ref "IC11") (pin "2") (pinfunction "D_2") (pintype "input"))
      (node (ref "IC11") (pin "3") (pinfunction "CLK_3") (pintype "input"))
      (node (ref "IC13") (pin "12") (pinfunction "I1_12") (pintype "input"))
      (node (ref "IC13") (pin "7") (pinfunction "I1_7") (pintype "input"))
      (node (ref "IC26") (pin "1") (pinfunction "A1_1") (pintype "input"))
      (node (ref "IC26") (pin "2") (pinfunction "A2_2") (pintype "input"))
      (node (ref "IC27") (pin "10") (pinfunction "I1_10") (pintype "input"))
      (node (ref "IC27") (pin "9") (pinfunction "I0_9") (pintype "input"))
      (node (ref "IC29") (pin "1") (pinfunction "A1_1") (pintype "input"))
      (node (ref "IC29") (pin "2") (pinfunction "A2_2") (pintype "input"))
      (node (ref "IC6") (pin "11") (pinfunction "I0_11") (pintype "input"))
      (node (ref "IC6") (pin "5") (pinfunction "I1_5") (pintype "input"))
      (node (ref "IC6") (pin "7") (pinfunction "I1_7") (pintype "input"))
      (node (ref "R13") (pin "2") (pinfunction "2_2") (pintype "passive"))
      (node (ref "R14") (pin "2") (pinfunction "2_2") (pintype "passive"))
      (node (ref "R19") (pin "2") (pinfunction "2_2") (pintype "passive"))
      (node (ref "U$2") (pin "AC2") (pinfunction "1_AC2") (pintype "bidirectional"))
      (node (ref "U$2") (pin "AF2") (pinfunction "1_AF2") (pintype "bidirectional"))
      (node (ref "U$2") (pin "BC2") (pinfunction "1_BC2") (pintype "bidirectional"))
      (node (ref "U$2") (pin "BF2") (pinfunction "1_BF2") (pintype "bidirectional"))
      (node (ref "U$2") (pin "CC2") (pinfunction "1_CC2") (pintype "bidirectional"))
      (node (ref "U$2") (pin "CF2") (pinfunction "1_CF2") (pintype "bidirectional"))
    )
    (net (code "43") (name "INITIALIZE") (class "Default")
      (node (ref "IC6") (pin "4") (pinfunction "I0_4") (pintype "input"))
      (node (ref "Q1") (pin "1") (pinfunction "E_1") (pintype "passive"))
      (node (ref "U$2") (pin "CR1") (pinfunction "1_CR1") (pintype "bidirectional"))
    )
    (net (code "44") (name "KS_OK") (class "Default")
      (node (ref "IC25") (pin "6") (pinfunction "O_6") (pintype "output"))
      (node (ref "IC30") (pin "13") (pinfunction "I3_13") (pintype "input"))
      (node (ref "IC30") (pin "5") (pinfunction "I3_5") (pintype "input"))
      (node (ref "IC34") (pin "13") (pinfunction "I3_13") (pintype "input"))
      (node (ref "IC34") (pin "5") (pinfunction "I3_5") (pintype "input"))
    )
    (net (code "45") (name "LA") (class "Default")
      (node (ref "IC22") (pin "1") (pinfunction "~{Q1}_1") (pintype "output"))
      (node (ref "IC34") (pin "1") (pinfunction "I0_1") (pintype "input"))
      (node (ref "IC34") (pin "2") (pinfunction "I1_2") (pintype "input"))
    )
    (net (code "46") (name "LA+DEP") (class "Default")
      (node (ref "IC18") (pin "9") (pinfunction "I1_9") (pintype "input"))
      (node (ref "IC19") (pin "10") (pinfunction "I1_10") (pintype "input"))
      (node (ref "IC21") (pin "6") (pinfunction "O_6") (pintype "output"))
    )
    (net (code "47") (name "LA+DEP+CONT") (class "Default")
      (node (ref "IC1") (pin "6") (pinfunction "O_6") (pintype "output"))
      (node (ref "IC10") (pin "1") (pinfunction "I0_1") (pintype "input"))
      (node (ref "IC19") (pin "4") (pinfunction "I2_4") (pintype "input"))
      (node (ref "IC19") (pin "5") (pinfunction "I3_5") (pintype "input"))
    )
    (net (code "48") (name "Net-(0-P)") (class "Default")
      (node (ref "0") (pin "1") (pinfunction "P_1") (pintype "passive"))
      (node (ref "IC25") (pin "11") (pinfunction "O_11") (pintype "output"))
    )
    (net (code "49") (name "Net-(1-P)") (class "Default")
      (node (ref "1") (pin "1") (pinfunction "P_1") (pintype "passive"))
      (node (ref "IC25") (pin "12") (pinfunction "I0_12") (pintype "input"))
      (node (ref "IC25") (pin "13") (pinfunction "I1_13") (pintype "input"))
      (node (ref "IC28") (pin "8") (pinfunction "O_8") (pintype "output"))
    )
    (net (code "50") (name "Net-(C5-Pad1)") (class "Default")
      (node (ref "C5") (pin "1") (pinfunction "1_1") (pintype "passive"))
      (node (ref "D5") (pin "C") (pinfunction "C_C") (pintype "passive"))
      (node (ref "R12") (pin "2") (pinfunction "2_2") (pintype "passive"))
      (node (ref "R14") (pin "1") (pinfunction "1_1") (pintype "passive"))
    )
    (net (code "51") (name "Net-(D3-PadA)") (class "Default")
      (node (ref "D3") (pin "A") (pinfunction "A_A") (pintype "passive"))
      (node (ref "R27") (pin "2") (pinfunction "2_2") (pintype "passive"))
    )
    (net (code "52") (name "Net-(H-P)") (class "Default")
      (node (ref "H") (pin "1") (pinfunction "P_1") (pintype "passive"))
      (node (ref "IC27") (pin "14") (pinfunction "O_14") (pintype "output"))
    )
    (net (code "53") (name "Net-(IC1B-I1)") (class "Default")
      (node (ref "IC1") (pin "10") (pinfunction "I1_10") (pintype "input"))
      (node (ref "IC6") (pin "2") (pinfunction "O_2") (pintype "output"))
    )
    (net (code "54") (name "Net-(IC1B-I2)") (class "Default")
      (node (ref "IC1") (pin "12") (pinfunction "I2_12") (pintype "input"))
      (node (ref "IC1") (pin "13") (pinfunction "I3_13") (pintype "input"))
      (node (ref "IC6") (pin "3") (pinfunction "O_3") (pintype "output"))
    )
    (net (code "55") (name "Net-(IC2A-I0)") (class "Default")
      (node (ref "IC2") (pin "2") (pinfunction "I0_2") (pintype "input"))
      (node (ref "IC2") (pin "3") (pinfunction "I1_3") (pintype "input"))
      (node (ref "IC3") (pin "6") (pinfunction "O_6") (pintype "output"))
    )
    (net (code "56") (name "Net-(IC2B-I0)") (class "Default")
      (node (ref "IC2") (pin "5") (pinfunction "I0_5") (pintype "input"))
      (node (ref "IC2") (pin "6") (pinfunction "I1_6") (pintype "input"))
      (node (ref "IC3") (pin "8") (pinfunction "O_8") (pintype "output"))
    )
    (net (code "57") (name "Net-(IC2C-O)") (class "Default")
      (node (ref "C39") (pin "1") (pinfunction "1_1") (pintype "passive"))
      (node (ref "D4") (pin "C") (pinfunction "C_C") (pintype "passive"))
      (node (ref "IC2") (pin "10") (pinfunction "O_10") (pintype "open_collector"))
      (node (ref "IC7") (pin "1") (pinfunction "I0_1") (pintype "input"))
      (node (ref "IC7") (pin "2") (pinfunction "I1_2") (pintype "input"))
      (node (ref "IC7") (pin "4") (pinfunction "I2_4") (pintype "input"))
      (node (ref "IC7") (pin "5") (pinfunction "I3_5") (pintype "input"))
      (node (ref "R26") (pin "1") (pinfunction "1_1") (pintype "passive"))
      (node (ref "R27") (pin "1") (pinfunction "1_1") (pintype "passive"))
    )
    (net (code "58") (name "Net-(IC6C-I0)") (class "Default")
      (node (ref "C25") (pin "1") (pinfunction "1_1") (pintype "passive"))
      (node (ref "IC6") (pin "9") (pinfunction "I0_9") (pintype "input"))
      (node (ref "R13") (pin "1") (pinfunction "1_1") (pintype "passive"))
    )
    (net (code "59") (name "Net-(IC6C-O)") (class "Default")
      (node (ref "C45") (pin "2") (pinfunction "2_2") (pintype "passive"))
      (node (ref "IC6") (pin "14") (pinfunction "O_14") (pintype "output"))
    )
    (net (code "60") (name "Net-(IC6D-I1)") (class "Default")
      (node (ref "C45") (pin "1") (pinfunction "1_1") (pintype "passive"))
      (node (ref "D5") (pin "A") (pinfunction "A_A") (pintype "passive"))
      (node (ref "IC6") (pin "12") (pinfunction "I1_12") (pintype "input"))
      (node (ref "R16") (pin "2") (pinfunction "2_2") (pintype "passive"))
    )
    (net (code "61") (name "Net-(IC7B-I2)") (class "Default")
      (node (ref "C40") (pin "1") (pinfunction "1_1") (pintype "passive"))
      (node (ref "IC7") (pin "12") (pinfunction "I2_12") (pintype "input"))
      (node (ref "IC7") (pin "13") (pinfunction "I3_13") (pintype "input"))
      (node (ref "R11") (pin "2") (pinfunction "2_2") (pintype "passive"))
    )
    (net (code "62") (name "Net-(IC9D-O)") (class "Default")
      (node (ref "IC9") (pin "8") (pinfunction "O_8") (pintype "output"))
      (node (ref "R11") (pin "1") (pinfunction "1_1") (pintype "passive"))
    )
    (net (code "63") (name "Net-(IC10A-O)") (class "Default")
      (node (ref "IC10") (pin "3") (pinfunction "O_3") (pintype "output"))
      (node (ref "IC10") (pin "4") (pinfunction "I0_4") (pintype "input"))
      (node (ref "IC10") (pin "5") (pinfunction "I1_5") (pintype "input"))
    )
    (net (code "64") (name "Net-(IC10B-O)") (class "Default")
      (node (ref "IC10") (pin "12") (pinfunction "I0_12") (pintype "input"))
      (node (ref "IC10") (pin "6") (pinfunction "O_6") (pintype "output"))
    )
    (net (code "65") (name "Net-(IC10C-I0)") (class "Default")
      (node (ref "IC1") (pin "8") (pinfunction "O_8") (pintype "output"))
      (node (ref "IC10") (pin "13") (pinfunction "I1_13") (pintype "input"))
      (node (ref "IC10") (pin "9") (pinfunction "I0_9") (pintype "input"))
    )
    (net (code "66") (name "Net-(IC10C-I1)") (class "Default")
      (node (ref "IC10") (pin "10") (pinfunction "I1_10") (pintype "input"))
      (node (ref "IC10") (pin "11") (pinfunction "O_11") (pintype "output"))
    )
    (net (code "67") (name "Net-(IC11A-CLR)") (class "Default")
      (node (ref "IC11") (pin "1") (pinfunction "CLR_1") (pintype "input"))
      (node (ref "R24") (pin "2") (pinfunction "2_2") (pintype "passive"))
      (node (ref "SET") (pin "1") (pinfunction "P_1") (pintype "passive"))
    )
    (net (code "68") (name "Net-(IC11A-PRE)") (class "Default")
      (node (ref "IC11") (pin "4") (pinfunction "PRE_4") (pintype "input"))
      (node (ref "R22") (pin "2") (pinfunction "2_2") (pintype "passive"))
      (node (ref "RES") (pin "1") (pinfunction "P_1") (pintype "passive"))
    )
    (net (code "69") (name "Net-(IC11A-Q)") (class "Default")
      (node (ref "IC11") (pin "5") (pinfunction "Q_5") (pintype "output"))
      (node (ref "IC7") (pin "10") (pinfunction "I1_10") (pintype "input"))
      (node (ref "IC7") (pin "9") (pinfunction "I0_9") (pintype "input"))
      (node (ref "IC9") (pin "9") (pinfunction "I_9") (pintype "input"))
    )
    (net (code "70") (name "Net-(IC11B-PRE)") (class "Default")
      (node (ref "IC11") (pin "10") (pinfunction "PRE_10") (pintype "input"))
      (node (ref "IC7") (pin "8") (pinfunction "O_8") (pintype "output"))
    )
    (net (code "71") (name "Net-(IC12A-I0)") (class "Default")
      (node (ref "IC12") (pin "2") (pinfunction "I0_2") (pintype "input"))
      (node (ref "IC12") (pin "3") (pinfunction "I1_3") (pintype "input"))
      (node (ref "IC8") (pin "11") (pinfunction "O_11") (pintype "output"))
    )
    (net (code "72") (name "Net-(IC12A-O)") (class "Default")
      (node (ref "IC12") (pin "1") (pinfunction "O_1") (pintype "open_collector"))
      (node (ref "R28") (pin "2") (pinfunction "2_2") (pintype "passive"))
      (node (ref "R6") (pin "2") (pinfunction "2_2") (pintype "passive"))
    )
    (net (code "73") (name "Net-(IC12C-I0)") (class "Default")
      (node (ref "IC12") (pin "8") (pinfunction "I0_8") (pintype "input"))
      (node (ref "IC12") (pin "9") (pinfunction "I1_9") (pintype "input"))
      (node (ref "IC8") (pin "6") (pinfunction "O_6") (pintype "output"))
    )
    (net (code "74") (name "Net-(IC12C-O)") (class "Default")
      (node (ref "IC12") (pin "10") (pinfunction "O_10") (pintype "open_collector"))
      (node (ref "R8") (pin "1") (pinfunction "1_1") (pintype "passive"))
      (node (ref "R9") (pin "1") (pinfunction "1_1") (pintype "passive"))
    )
    (net (code "75") (name "Net-(IC13A-O)") (class "Default")
      (node (ref "IC13") (pin "3") (pinfunction "O_3") (pintype "output"))
      (node (ref "R15") (pin "2") (pinfunction "2_2") (pintype "passive"))
    )
    (net (code "76") (name "Net-(IC14A-I0)") (class "Default")
      (node (ref "D3") (pin "C") (pinfunction "C_C") (pintype "passive"))
      (node (ref "IC14") (pin "1") (pinfunction "I0_1") (pintype "input"))
      (node (ref "IC14") (pin "2") (pinfunction "I1_2") (pintype "input"))
      (node (ref "IC2") (pin "8") (pinfunction "I0_8") (pintype "input"))
      (node (ref "IC7") (pin "6") (pinfunction "O_6") (pintype "output"))
      (node (ref "R26") (pin "2") (pinfunction "2_2") (pintype "passive"))
    )
    (net (code "77") (name "Net-(IC14B-O)") (class "Default")
      (node (ref "IC14") (pin "10") (pinfunction "I1_10") (pintype "input"))
      (node (ref "IC14") (pin "6") (pinfunction "O_6") (pintype "output"))
      (node (ref "IC14") (pin "9") (pinfunction "I0_9") (pintype "input"))
    )
    (net (code "78") (name "Net-(IC14C-O)") (class "Default")
      (node (ref "IC14") (pin "8") (pinfunction "O_8") (pintype "output"))
      (node (ref "IC17") (pin "14") (pinfunction "CKA_14") (pintype "input"))
    )
    (net (code "79") (name "Net-(IC15A-I1)") (class "Default")
      (node (ref "IC15") (pin "12") (pinfunction "I1_12") (pintype "input"))
      (node (ref "IC15") (pin "3") (pinfunction "I1_3") (pintype "input"))
      (node (ref "IC15") (pin "6") (pinfunction "I1_6") (pintype "input"))
      (node (ref "IC15") (pin "9") (pinfunction "I1_9") (pintype "input"))
      (node (ref "IC31") (pin "12") (pinfunction "I1_12") (pintype "input"))
      (node (ref "IC31") (pin "3") (pinfunction "I1_3") (pintype "input"))
      (node (ref "IC31") (pin "6") (pinfunction "I1_6") (pintype "input"))
      (node (ref "IC31") (pin "9") (pinfunction "I1_9") (pintype "input"))
      (node (ref "IC4") (pin "11") (pinfunction "I0_11") (pintype "input"))
      (node (ref "IC4") (pin "3") (pinfunction "I1_3") (pintype "input"))
      (node (ref "IC4") (pin "6") (pinfunction "I1_6") (pintype "input"))
      (node (ref "IC4") (pin "9") (pinfunction "I1_9") (pintype "input"))
      (node (ref "IC9") (pin "10") (pinfunction "O_10") (pintype "output"))
      (node (ref "IC9") (pin "12") (pinfunction "O_12") (pintype "output"))
    )
    (net (code "80") (name "Net-(IC19A-I0)") (class "Default")
      (node (ref "C4") (pin "1") (pinfunction "1_1") (pintype "passive"))
      (node (ref "IC19") (pin "1") (pinfunction "I0_1") (pintype "input"))
      (node (ref "IC19") (pin "2") (pinfunction "I1_2") (pintype "input"))
      (node (ref "R15") (pin "1") (pinfunction "1_1") (pintype "passive"))
    )
    (net (code "81") (name "Net-(IC19A-O)") (class "Default")
      (node (ref "IC19") (pin "6") (pinfunction "O_6") (pintype "output"))
      (node (ref "R4") (pin "1") (pinfunction "1_1") (pintype "passive"))
    )
    (net (code "82") (name "Net-(IC19B-O)") (class "Default")
      (node (ref "IC19") (pin "8") (pinfunction "O_8") (pintype "output"))
      (node (ref "IC9") (pin "11") (pinfunction "I_11") (pintype "input"))
      (node (ref "IC9") (pin "13") (pinfunction "I_13") (pintype "input"))
    )
    (net (code "83") (name "Net-(IC25A-I1)") (class "Default")
      (node (ref "IC25") (pin "2") (pinfunction "I1_2") (pintype "input"))
      (node (ref "IC27") (pin "2") (pinfunction "O_2") (pintype "output"))
    )
    (net (code "84") (name "Net-(IC25A-O)") (class "Default")
      (node (ref "IC25") (pin "3") (pinfunction "O_3") (pintype "output"))
      (node (ref "IC25") (pin "4") (pinfunction "I0_4") (pintype "input"))
    )
    (net (code "85") (name "Net-(IC26A-B1)") (class "Default")
      (node (ref "IC26") (pin "3") (pinfunction "B1_3") (pintype "input"))
      (node (ref "IC26") (pin "4") (pinfunction "B2_4") (pintype "input"))
      (node (ref "IC30") (pin "6") (pinfunction "O_6") (pintype "output"))
    )
    (net (code "86") (name "Net-(IC26A-C)") (class "Default")
      (node (ref "C41") (pin "2") (pinfunction "2_2") (pintype "passive"))
      (node (ref "IC26") (pin "11") (pinfunction "C_11") (pintype "input"))
    )
    (net (code "87") (name "Net-(IC26A-R{slash}C)") (class "Default")
      (node (ref "C41") (pin "1") (pinfunction "1_1") (pintype "passive"))
      (node (ref "IC26") (pin "13") (pinfunction "R/C_13") (pintype "input"))
      (node (ref "R17") (pin "2") (pinfunction "2_2") (pintype "passive"))
    )
    (net (code "88") (name "Net-(IC27A-O)") (class "Default")
      (node (ref "IC27") (pin "3") (pinfunction "O_3") (pintype "output"))
      (node (ref "R3") (pin "2") (pinfunction "2_2") (pintype "passive"))
    )
    (net (code "89") (name "Net-(IC27B-I0)") (class "Default")
      (node (ref "IC27") (pin "6") (pinfunction "I0_6") (pintype "input"))
      (node (ref "IC27") (pin "7") (pinfunction "I1_7") (pintype "input"))
      (node (ref "KS") (pin "1") (pinfunction "P_1") (pintype "passive"))
    )
    (net (code "90") (name "Net-(IC28A-I0)") (class "Default")
      (node (ref "C33") (pin "1") (pinfunction "1_1") (pintype "passive"))
      (node (ref "IC28") (pin "1") (pinfunction "I0_1") (pintype "input"))
      (node (ref "IC28") (pin "2") (pinfunction "I1_2") (pintype "input"))
      (node (ref "IC28") (pin "4") (pinfunction "I2_4") (pintype "input"))
      (node (ref "IC28") (pin "5") (pinfunction "I3_5") (pintype "input"))
      (node (ref "R4") (pin "2") (pinfunction "2_2") (pintype "passive"))
    )
    (net (code "91") (name "Net-(IC28A-O)") (class "Default")
      (node (ref "C25") (pin "2") (pinfunction "2_2") (pintype "passive"))
      (node (ref "IC28") (pin "6") (pinfunction "O_6") (pintype "output"))
    )
    (net (code "92") (name "Net-(IC28B-I0)") (class "Default")
      (node (ref "D2") (pin "C") (pinfunction "C_C") (pintype "passive"))
      (node (ref "IC28") (pin "10") (pinfunction "I1_10") (pintype "input"))
      (node (ref "IC28") (pin "12") (pinfunction "I2_12") (pintype "input"))
      (node (ref "IC28") (pin "13") (pinfunction "I3_13") (pintype "input"))
      (node (ref "IC28") (pin "9") (pinfunction "I0_9") (pintype "input"))
      (node (ref "Q2") (pin "1") (pinfunction "E_1") (pintype "passive"))
      (node (ref "R1") (pin "2") (pinfunction "2_2") (pintype "passive"))
    )
    (net (code "93") (name "Net-(IC29A-C)") (class "Default")
      (node (ref "C44") (pin "2") (pinfunction "2_2") (pintype "passive"))
      (node (ref "IC29") (pin "11") (pinfunction "C_11") (pintype "input"))
    )
    (net (code "94") (name "Net-(IC29A-Q)") (class "Default")
      (node (ref "IC29") (pin "8") (pinfunction "Q_8") (pintype "output"))
      (node (ref "IC33") (pin "1") (pinfunction "A1_1") (pintype "input"))
      (node (ref "IC33") (pin "2") (pinfunction "A2_2") (pintype "input"))
    )
    (net (code "95") (name "Net-(IC29A-R{slash}C)") (class "Default")
      (node (ref "C44") (pin "1") (pinfunction "1_1") (pintype "passive"))
      (node (ref "IC29") (pin "13") (pinfunction "R/C_13") (pintype "input"))
      (node (ref "R21") (pin "2") (pinfunction "2_2") (pintype "passive"))
    )
    (net (code "96") (name "Net-(IC33A-B1)") (class "Default")
      (node (ref "C43") (pin "1") (pinfunction "1_1") (pintype "passive"))
      (node (ref "IC33") (pin "3") (pinfunction "B1_3") (pintype "input"))
      (node (ref "IC33") (pin "4") (pinfunction "B2_4") (pintype "input"))
      (node (ref "R19") (pin "1") (pinfunction "1_1") (pintype "passive"))
      (node (ref "R23") (pin "2") (pinfunction "2_2") (pintype "passive"))
    )
    (net (code "97") (name "Net-(IC33A-C)") (class "Default")
      (node (ref "C42") (pin "2") (pinfunction "2_2") (pintype "passive"))
      (node (ref "IC33") (pin "11") (pinfunction "C_11") (pintype "input"))
    )
    (net (code "98") (name "Net-(IC33A-R{slash}C)") (class "Default")
      (node (ref "C42") (pin "1") (pinfunction "1_1") (pintype "passive"))
      (node (ref "IC33") (pin "13") (pinfunction "R/C_13") (pintype "input"))
      (node (ref "R25") (pin "2") (pinfunction "2_2") (pintype "passive"))
    )
    (net (code "99") (name "Net-(Q1-B)") (class "Default")
      (node (ref "Q1") (pin "2") (pinfunction "B_2") (pintype "passive"))
      (node (ref "R8") (pin "2") (pinfunction "2_2") (pintype "passive"))
    )
    (net (code "100") (name "Net-(Q1-C)") (class "Default")
      (node (ref "Q1") (pin "3") (pinfunction "C_3") (pintype "passive"))
      (node (ref "R10") (pin "1") (pinfunction "1_1") (pintype "passive"))
    )
    (net (code "101") (name "Net-(Q2-B)") (class "Default")
      (node (ref "C7") (pin "+") (pinfunction "+_+") (pintype "passive"))
      (node (ref "Q2") (pin "2") (pinfunction "B_2") (pintype "passive"))
      (node (ref "R3") (pin "1") (pinfunction "1_1") (pintype "passive"))
    )
    (net (code "102") (name "Net-(Q2-C)") (class "Default")
      (node (ref "Q2") (pin "3") (pinfunction "C_3") (pintype "passive"))
      (node (ref "R2") (pin "1") (pinfunction "1_1") (pintype "passive"))
    )
    (net (code "103") (name "Net-(Q3-B)") (class "Default")
      (node (ref "Q3") (pin "2") (pinfunction "B_2") (pintype "passive"))
      (node (ref "R6") (pin "1") (pinfunction "1_1") (pintype "passive"))
    )
    (net (code "104") (name "Net-(Q3-C)") (class "Default")
      (node (ref "Q3") (pin "3") (pinfunction "C_3") (pintype "passive"))
      (node (ref "R5") (pin "2") (pinfunction "2_2") (pintype "passive"))
    )
    (net (code "105") (name "Net-(U$2AU-1)") (class "Default")
      (node (ref "U$2") (pin "BF1") (pinfunction "1_BF1") (pintype "bidirectional"))
      (node (ref "U$2") (pin "BN1") (pinfunction "1_BN1") (pintype "bidirectional"))
    )
    (net (code "106") (name "Net-(U$2CZ-1)") (class "Default")
      (node (ref "U$2") (pin "CT2") (pinfunction "1_CT2") (pintype "bidirectional"))
      (node (ref "U$2") (pin "DF2") (pinfunction "1_DF2") (pintype "bidirectional"))
      (node (ref "U$2") (pin "DN2") (pinfunction "1_DN2") (pintype "bidirectional"))
    )
    (net (code "107") (name "Net-(U$2D-1)") (class "Default")
      (node (ref "R7") (pin "1") (pinfunction "1_1") (pintype "passive"))
      (node (ref "U$2") (pin "AB2") (pinfunction "1_AB2") (pintype "bidirectional"))
    )
    (net (code "108") (name "Net-(U$2DO-1)") (class "Default")
      (node (ref "U$2") (pin "DF1") (pinfunction "1_DF1") (pintype "bidirectional"))
      (node (ref "U$2") (pin "DN1") (pinfunction "1_DN1") (pintype "bidirectional"))
    )
    (net (code "109") (name "Net-(U$2K-1)") (class "Default")
      (node (ref "U$2") (pin "AF1") (pinfunction "1_AF1") (pintype "bidirectional"))
      (node (ref "U$2") (pin "AN1") (pinfunction "1_AN1") (pintype "bidirectional"))
    )
    (net (code "110") (name "ODD") (class "Default")
      (node (ref "IC2") (pin "1") (pinfunction "O_1") (pintype "open_collector"))
      (node (ref "IC22") (pin "13") (pinfunction "C12_13") (pintype "input"))
      (node (ref "IC22") (pin "4") (pinfunction "C34_4") (pintype "input"))
      (node (ref "IC29") (pin "3") (pinfunction "B1_3") (pintype "input"))
      (node (ref "IC29") (pin "4") (pinfunction "B2_4") (pintype "input"))
      (node (ref "IC32") (pin "13") (pinfunction "C12_13") (pintype "input"))
      (node (ref "IC32") (pin "4") (pinfunction "C34_4") (pintype "input"))
      (node (ref "R20") (pin "2") (pinfunction "2_2") (pintype "passive"))
    )
    (net (code "111") (name "PULSE") (class "Default")
      (node (ref "IC12") (pin "5") (pinfunction "I0_5") (pintype "input"))
      (node (ref "IC6") (pin "10") (pinfunction "I1_10") (pintype "input"))
      (node (ref "IC6") (pin "13") (pinfunction "O_13") (pintype "output"))
      (node (ref "IC8") (pin "13") (pinfunction "I1_13") (pintype "input"))
      (node (ref "IC8") (pin "5") (pinfunction "I1_5") (pintype "input"))
    )
    (net (code "112") (name "PULSE_LA") (class "Default")
      (node (ref "Q3") (pin "1") (pinfunction "E_1") (pintype "passive"))
      (node (ref "U$2") (pin "DR2") (pinfunction "1_DR2") (pintype "bidirectional"))
    )
    (net (code "113") (name "SWITCH") (class "Default")
      (node (ref "IC27") (pin "4") (pinfunction "I0_4") (pintype "input"))
      (node (ref "IC27") (pin "5") (pinfunction "I1_5") (pintype "input"))
      (node (ref "N") (pin "1") (pinfunction "P_1") (pintype "passive"))
      (node (ref "U$2") (pin "DV2") (pinfunction "1_DV2") (pintype "bidirectional"))
    )
    (net (code "114") (name "TIMER1") (class "Default")
      (node (ref "IC25") (pin "8") (pinfunction "O_8") (pintype "output"))
      (node (ref "IC30") (pin "10") (pinfunction "I1_10") (pintype "input"))
      (node (ref "IC30") (pin "9") (pinfunction "I0_9") (pintype "input"))
    )
    (net (code "115") (name "TIMER2") (class "Default")
      (node (ref "IC30") (pin "4") (pinfunction "I2_4") (pintype "input"))
      (node (ref "IC33") (pin "8") (pinfunction "Q_8") (pintype "output"))
      (node (ref "IC34") (pin "12") (pinfunction "I2_12") (pintype "input"))
      (node (ref "IC34") (pin "4") (pinfunction "I2_4") (pintype "input"))
    )
    (net (code "116") (name "TP4") (class "Default")
      (node (ref "IC6") (pin "6") (pinfunction "I0_6") (pintype "input"))
      (node (ref "U$2") (pin "CJ2") (pinfunction "1_CJ2") (pintype "bidirectional"))
    )
    (net (code "117") (name "TS4L") (class "Default")
      (node (ref "IC13") (pin "13") (pinfunction "O_13") (pintype "output"))
      (node (ref "IC19") (pin "12") (pinfunction "I2_12") (pintype "input"))
      (node (ref "IC19") (pin "13") (pinfunction "I3_13") (pintype "input"))
    )
    (net (code "118") (name "VCC") (class "Default")
      (node (ref "C1") (pin "1") (pinfunction "1_1") (pintype "passive"))
      (node (ref "C11") (pin "1") (pinfunction "1_1") (pintype "passive"))
      (node (ref "C12") (pin "1") (pinfunction "1_1") (pintype "passive"))
      (node (ref "C15") (pin "1") (pinfunction "1_1") (pintype "passive"))
      (node (ref "C16") (pin "1") (pinfunction "1_1") (pintype "passive"))
      (node (ref "C18") (pin "1") (pinfunction "1_1") (pintype "passive"))
      (node (ref "C2") (pin "1") (pinfunction "1_1") (pintype "passive"))
      (node (ref "C21") (pin "1") (pinfunction "1_1") (pintype "passive"))
      (node (ref "C24") (pin "1") (pinfunction "1_1") (pintype "passive"))
      (node (ref "C28") (pin "1") (pinfunction "1_1") (pintype "passive"))
      (node (ref "C29") (pin "1") (pinfunction "1_1") (pintype "passive"))
      (node (ref "C3") (pin "1") (pinfunction "1_1") (pintype "passive"))
      (node (ref "C31") (pin "1") (pinfunction "1_1") (pintype "passive"))
      (node (ref "C32") (pin "1") (pinfunction "1_1") (pintype "passive"))
      (node (ref "C34") (pin "+") (pinfunction "+_+") (pintype "passive"))
      (node (ref "C35") (pin "+") (pinfunction "+_+") (pintype "passive"))
      (node (ref "C36") (pin "+") (pinfunction "+_+") (pintype "passive"))
      (node (ref "C6") (pin "1") (pinfunction "1_1") (pintype "passive"))
      (node (ref "IC20") (pin "12") (pinfunction "VCC1_12") (pintype "input"))
      (node (ref "IC20") (pin "13") (pinfunction "P_13") (pintype "input"))
      (node (ref "IC20") (pin "15") (pinfunction "VBB_15") (pintype "input"))
      (node (ref "IC20") (pin "22") (pinfunction "VCC2_22") (pintype "input"))
      (node (ref "IC20") (pin "23") (pinfunction "VCC3_23") (pintype "input"))
      (node (ref "R10") (pin "2") (pinfunction "2_2") (pintype "passive"))
      (node (ref "R12") (pin "1") (pinfunction "1_1") (pintype "passive"))
      (node (ref "R16") (pin "1") (pinfunction "1_1") (pintype "passive"))
      (node (ref "R17") (pin "1") (pinfunction "1_1") (pintype "passive"))
      (node (ref "R18") (pin "1") (pinfunction "1_1") (pintype "passive"))
      (node (ref "R2") (pin "2") (pinfunction "2_2") (pintype "passive"))
      (node (ref "R20") (pin "1") (pinfunction "1_1") (pintype "passive"))
      (node (ref "R21") (pin "1") (pinfunction "1_1") (pintype "passive"))
      (node (ref "R22") (pin "1") (pinfunction "1_1") (pintype "passive"))
      (node (ref "R23") (pin "1") (pinfunction "1_1") (pintype "passive"))
      (node (ref "R24") (pin "1") (pinfunction "1_1") (pintype "passive"))
      (node (ref "R25") (pin "1") (pinfunction "1_1") (pintype "passive"))
      (node (ref "R28") (pin "1") (pinfunction "1_1") (pintype "passive"))
      (node (ref "R5") (pin "1") (pinfunction "1_1") (pintype "passive"))
      (node (ref "R9") (pin "2") (pinfunction "2_2") (pintype "passive"))
      (node (ref "U$2") (pin "AA2") (pinfunction "1_AA2") (pintype "bidirectional"))
      (node (ref "U$2") (pin "BA2") (pinfunction "1_BA2") (pintype "bidirectional"))
      (node (ref "U$2") (pin "CA2") (pinfunction "1_CA2") (pintype "bidirectional"))
    )
    (net (code "119") (name "VDD") (class "Default")
      (node (ref "C19") (pin "2") (pinfunction "2_2") (pintype "passive"))
      (node (ref "C37") (pin "-") (pinfunction "-_-") (pintype "passive"))
      (node (ref "D1") (pin "A") (pinfunction "A_A") (pintype "passive"))
      (node (ref "IC20") (pin "16") (pinfunction "VGG_16") (pintype "input"))
      (node (ref "IC20") (pin "24") (pinfunction "VDD_24") (pintype "input"))
      (node (ref "R7") (pin "2") (pinfunction "2_2") (pintype "passive"))
    )
    (net (code "120") (name "unconnected-(IC5A-Q1-Pad16)") (class "Default")
      (node (ref "IC5") (pin "16") (pinfunction "Q1_16") (pintype "output"))
    )
    (net (code "121") (name "unconnected-(IC5A-Q2-Pad15)") (class "Default")
      (node (ref "IC5") (pin "15") (pinfunction "Q2_15") (pintype "output"))
    )
    (net (code "122") (name "unconnected-(IC5A-Q3-Pad10)") (class "Default")
      (node (ref "IC5") (pin "10") (pinfunction "Q3_10") (pintype "output"))
    )
    (net (code "123") (name "unconnected-(IC5A-Q4-Pad9)") (class "Default")
      (node (ref "IC5") (pin "9") (pinfunction "Q4_9") (pintype "output"))
    )
    (net (code "124") (name "unconnected-(IC11A-~{Q}-Pad6)") (class "Default")
      (node (ref "IC11") (pin "6") (pinfunction "~{Q}_6") (pintype "output"))
    )
    (net (code "125") (name "unconnected-(IC16A-Q1-Pad16)") (class "Default")
      (node (ref "IC16") (pin "16") (pinfunction "Q1_16") (pintype "output"))
    )
    (net (code "126") (name "unconnected-(IC16A-Q2-Pad15)") (class "Default")
      (node (ref "IC16") (pin "15") (pinfunction "Q2_15") (pintype "output"))
    )
    (net (code "127") (name "unconnected-(IC16A-Q3-Pad10)") (class "Default")
      (node (ref "IC16") (pin "10") (pinfunction "Q3_10") (pintype "output"))
    )
    (net (code "128") (name "unconnected-(IC16A-Q4-Pad9)") (class "Default")
      (node (ref "IC16") (pin "9") (pinfunction "Q4_9") (pintype "output"))
    )
    (net (code "129") (name "unconnected-(IC22A-Q1-Pad16)") (class "Default")
      (node (ref "IC22") (pin "16") (pinfunction "Q1_16") (pintype "output"))
    )
    (net (code "130") (name "unconnected-(IC22A-Q2-Pad15)") (class "Default")
      (node (ref "IC22") (pin "15") (pinfunction "Q2_15") (pintype "output"))
    )
    (net (code "131") (name "unconnected-(IC22A-Q3-Pad10)") (class "Default")
      (node (ref "IC22") (pin "10") (pinfunction "Q3_10") (pintype "output"))
    )
    (net (code "132") (name "unconnected-(IC22A-Q4-Pad9)") (class "Default")
      (node (ref "IC22") (pin "9") (pinfunction "Q4_9") (pintype "output"))
    )
    (net (code "133") (name "unconnected-(IC26A-CLR-Pad5)") (class "Default")
      (node (ref "IC26") (pin "5") (pinfunction "CLR_5") (pintype "input"))
    )
    (net (code "134") (name "unconnected-(IC26A-Q-Pad8)") (class "Default")
      (node (ref "IC26") (pin "8") (pinfunction "Q_8") (pintype "output"))
    )
    (net (code "135") (name "unconnected-(IC26A-R-Pad9)") (class "Default")
      (node (ref "IC26") (pin "9") (pinfunction "R_9") (pintype "input"))
    )
    (net (code "136") (name "unconnected-(IC29A-CLR-Pad5)") (class "Default")
      (node (ref "IC29") (pin "5") (pinfunction "CLR_5") (pintype "input"))
    )
    (net (code "137") (name "unconnected-(IC29A-R-Pad9)") (class "Default")
      (node (ref "IC29") (pin "9") (pinfunction "R_9") (pintype "input"))
    )
    (net (code "138") (name "unconnected-(IC32A-Q1-Pad16)") (class "Default")
      (node (ref "IC32") (pin "16") (pinfunction "Q1_16") (pintype "output"))
    )
    (net (code "139") (name "unconnected-(IC32A-Q2-Pad15)") (class "Default")
      (node (ref "IC32") (pin "15") (pinfunction "Q2_15") (pintype "output"))
    )
    (net (code "140") (name "unconnected-(IC32A-Q3-Pad10)") (class "Default")
      (node (ref "IC32") (pin "10") (pinfunction "Q3_10") (pintype "output"))
    )
    (net (code "141") (name "unconnected-(IC32A-Q4-Pad9)") (class "Default")
      (node (ref "IC32") (pin "9") (pinfunction "Q4_9") (pintype "output"))
    )
    (net (code "142") (name "unconnected-(IC33A-CLR-Pad5)") (class "Default")
      (node (ref "IC33") (pin "5") (pinfunction "CLR_5") (pintype "input"))
    )
    (net (code "143") (name "unconnected-(IC33A-R-Pad9)") (class "Default")
      (node (ref "IC33") (pin "9") (pinfunction "R_9") (pintype "input"))
    )
    (net (code "144") (name "unconnected-(IC33A-~{Q}-Pad6)") (class "Default")
      (node (ref "IC33") (pin "6") (pinfunction "~{Q}_6") (pintype "output"))
    )
    (net (code "145") (name "~{A0}") (class "Default")
      (node (ref "IC3") (pin "12") (pinfunction "I2_12") (pintype "input"))
      (node (ref "IC3") (pin "13") (pinfunction "I3_13") (pintype "input"))
      (node (ref "IC9") (pin "6") (pinfunction "O_6") (pintype "output"))
    )
    (net (code "146") (name "~{ACTIVE}") (class "Default")
      (node (ref "IC11") (pin "8") (pinfunction "~{Q}_8") (pintype "output"))
      (node (ref "IC17") (pin "2") (pinfunction "R0(1)_2") (pintype "input"))
      (node (ref "IC17") (pin "3") (pinfunction "R0(2)_3") (pintype "input"))
      (node (ref "IC2") (pin "9") (pinfunction "I1_9") (pintype "input"))
      (node (ref "IC24") (pin "2") (pinfunction "R0(1)_2") (pintype "input"))
      (node (ref "IC24") (pin "3") (pinfunction "R0(2)_3") (pintype "input"))
    )
    (net (code "147") (name "~{BRK_DATA_CONT}") (class "Default")
      (node (ref "IC12") (pin "13") (pinfunction "O_13") (pintype "open_collector"))
      (node (ref "U$2") (pin "BK2") (pinfunction "1_BK2") (pintype "bidirectional"))
    )
    (net (code "148") (name "~{BRUN}") (class "Default")
      (node (ref "IC13") (pin "6") (pinfunction "I0_6") (pintype "input"))
      (node (ref "U$2") (pin "BU2") (pinfunction "1_BU2") (pintype "bidirectional"))
    )
    (net (code "149") (name "~{CS}") (class "Default")
      (node (ref "IC14") (pin "11") (pinfunction "O_11") (pintype "output"))
      (node (ref "IC20") (pin "14") (pinfunction "~{CS}_14") (pintype "input"))
    )
    (net (code "150") (name "~{D0}") (class "Default")
      (node (ref "IC16") (pin "7") (pinfunction "D4_7") (pintype "input"))
      (node (ref "IC22") (pin "7") (pinfunction "D4_7") (pintype "input"))
      (node (ref "IC23") (pin "2") (pinfunction "O_2") (pintype "output"))
    )
    (net (code "151") (name "~{D1}") (class "Default")
      (node (ref "IC16") (pin "6") (pinfunction "D3_6") (pintype "input"))
      (node (ref "IC22") (pin "6") (pinfunction "D3_6") (pintype "input"))
      (node (ref "IC23") (pin "4") (pinfunction "O_4") (pintype "output"))
    )
    (net (code "152") (name "~{D2}") (class "Default")
      (node (ref "IC16") (pin "3") (pinfunction "D2_3") (pintype "input"))
      (node (ref "IC22") (pin "3") (pinfunction "D2_3") (pintype "input"))
      (node (ref "IC23") (pin "6") (pinfunction "O_6") (pintype "output"))
    )
    (net (code "153") (name "~{D3}") (class "Default")
      (node (ref "IC16") (pin "2") (pinfunction "D1_2") (pintype "input"))
      (node (ref "IC22") (pin "2") (pinfunction "D1_2") (pintype "input"))
      (node (ref "IC23") (pin "8") (pinfunction "O_8") (pintype "output"))
    )
    (net (code "154") (name "~{D4}") (class "Default")
      (node (ref "IC23") (pin "10") (pinfunction "O_10") (pintype "output"))
      (node (ref "IC32") (pin "7") (pinfunction "D4_7") (pintype "input"))
      (node (ref "IC5") (pin "7") (pinfunction "D4_7") (pintype "input"))
    )
    (net (code "155") (name "~{D5}") (class "Default")
      (node (ref "IC23") (pin "12") (pinfunction "O_12") (pintype "output"))
      (node (ref "IC32") (pin "6") (pinfunction "D3_6") (pintype "input"))
      (node (ref "IC5") (pin "6") (pinfunction "D3_6") (pintype "input"))
    )
    (net (code "156") (name "~{D6}") (class "Default")
      (node (ref "IC32") (pin "3") (pinfunction "D2_3") (pintype "input"))
      (node (ref "IC5") (pin "3") (pinfunction "D2_3") (pintype "input"))
      (node (ref "IC9") (pin "2") (pinfunction "O_2") (pintype "output"))
    )
    (net (code "157") (name "~{D7}") (class "Default")
      (node (ref "IC32") (pin "2") (pinfunction "D1_2") (pintype "input"))
      (node (ref "IC5") (pin "2") (pinfunction "D1_2") (pintype "input"))
      (node (ref "IC9") (pin "4") (pinfunction "O_4") (pintype "output"))
    )
    (net (code "158") (name "~{DATA0}") (class "Default")
      (node (ref "IC4") (pin "13") (pinfunction "O_13") (pintype "open_collector"))
      (node (ref "U$2") (pin "AR1") (pinfunction "1_AR1") (pintype "bidirectional"))
    )
    (net (code "159") (name "~{DATA1}") (class "Default")
      (node (ref "IC4") (pin "10") (pinfunction "O_10") (pintype "open_collector"))
      (node (ref "U$2") (pin "AS1") (pinfunction "1_AS1") (pintype "bidirectional"))
    )
    (net (code "160") (name "~{DATA2}") (class "Default")
      (node (ref "IC4") (pin "4") (pinfunction "O_4") (pintype "open_collector"))
      (node (ref "U$2") (pin "AU1") (pinfunction "1_AU1") (pintype "bidirectional"))
    )
    (net (code "161") (name "~{DATA3}") (class "Default")
      (node (ref "IC4") (pin "1") (pinfunction "O_1") (pintype "open_collector"))
      (node (ref "U$2") (pin "AV1") (pinfunction "1_AV1") (pintype "bidirectional"))
    )
    (net (code "162") (name "~{DATA4}") (class "Default")
      (node (ref "IC15") (pin "13") (pinfunction "O_13") (pintype "open_collector"))
      (node (ref "U$2") (pin "BR1") (pinfunction "1_BR1") (pintype "bidirectional"))
    )
    (net (code "163") (name "~{DATA5}") (class "Default")
      (node (ref "IC15") (pin "10") (pinfunction "O_10") (pintype "open_collector"))
      (node (ref "U$2") (pin "BS1") (pinfunction "1_BS1") (pintype "bidirectional"))
    )
    (net (code "164") (name "~{DATA6}") (class "Default")
      (node (ref "IC15") (pin "4") (pinfunction "O_4") (pintype "open_collector"))
      (node (ref "U$2") (pin "BU1") (pinfunction "1_BU1") (pintype "bidirectional"))
    )
    (net (code "165") (name "~{DATA7}") (class "Default")
      (node (ref "IC15") (pin "1") (pinfunction "O_1") (pintype "open_collector"))
      (node (ref "U$2") (pin "BV1") (pinfunction "1_BV1") (pintype "bidirectional"))
    )
    (net (code "166") (name "~{DATA8}") (class "Default")
      (node (ref "IC31") (pin "13") (pinfunction "O_13") (pintype "open_collector"))
      (node (ref "U$2") (pin "DR1") (pinfunction "1_DR1") (pintype "bidirectional"))
    )
    (net (code "167") (name "~{DATA9}") (class "Default")
      (node (ref "IC31") (pin "10") (pinfunction "O_10") (pintype "open_collector"))
      (node (ref "U$2") (pin "DS1") (pinfunction "1_DS1") (pintype "bidirectional"))
    )
    (net (code "168") (name "~{DATA10}") (class "Default")
      (node (ref "IC31") (pin "4") (pinfunction "O_4") (pintype "open_collector"))
      (node (ref "U$2") (pin "DU1") (pinfunction "1_DU1") (pintype "bidirectional"))
    )
    (net (code "169") (name "~{DATA11}") (class "Default")
      (node (ref "IC31") (pin "1") (pinfunction "O_1") (pintype "open_collector"))
      (node (ref "U$2") (pin "DV1") (pinfunction "1_DV1") (pintype "bidirectional"))
    )
    (net (code "170") (name "~{DOCLR}") (class "Default")
      (node (ref "IC1") (pin "5") (pinfunction "I3_5") (pintype "input"))
      (node (ref "IC30") (pin "8") (pinfunction "O_8") (pintype "output"))
      (node (ref "IC8") (pin "1") (pinfunction "I0_1") (pintype "input"))
      (node (ref "IC8") (pin "2") (pinfunction "I1_2") (pintype "input"))
    )
    (net (code "171") (name "~{DODEP}") (class "Default")
      (node (ref "IC1") (pin "2") (pinfunction "I1_2") (pintype "input"))
      (node (ref "IC21") (pin "1") (pinfunction "I0_1") (pintype "input"))
      (node (ref "IC21") (pin "2") (pinfunction "I1_2") (pintype "input"))
      (node (ref "IC21") (pin "5") (pinfunction "I1_5") (pintype "input"))
      (node (ref "IC34") (pin "8") (pinfunction "O_8") (pintype "output"))
      (node (ref "IC8") (pin "9") (pinfunction "I0_9") (pintype "input"))
    )
    (net (code "172") (name "~{DOLA}") (class "Default")
      (node (ref "IC1") (pin "1") (pinfunction "I0_1") (pintype "input"))
      (node (ref "IC21") (pin "10") (pinfunction "I1_10") (pintype "input"))
      (node (ref "IC21") (pin "4") (pinfunction "I0_4") (pintype "input"))
      (node (ref "IC21") (pin "9") (pinfunction "I0_9") (pintype "input"))
      (node (ref "IC34") (pin "6") (pinfunction "O_6") (pintype "output"))
    )
    (net (code "173") (name "~{KEY_CONT}") (class "Default")
      (node (ref "IC18") (pin "4") (pinfunction "O_4") (pintype "open_collector"))
      (node (ref "U$2") (pin "DU2") (pinfunction "1_DU2") (pintype "bidirectional"))
    )
    (net (code "174") (name "~{LA_ENABLE}") (class "Default")
      (node (ref "IC18") (pin "1") (pinfunction "O_1") (pintype "open_collector"))
      (node (ref "U$2") (pin "BM2") (pinfunction "1_BM2") (pintype "bidirectional"))
    )
    (net (code "175") (name "~{MD_DIR}") (class "Default")
      (node (ref "IC18") (pin "13") (pinfunction "O_13") (pintype "open_collector"))
      (node (ref "U$2") (pin "AK2") (pinfunction "1_AK2") (pintype "bidirectional"))
    )
    (net (code "176") (name "~{MEM_START}") (class "Default")
      (node (ref "IC12") (pin "4") (pinfunction "O_4") (pintype "open_collector"))
      (node (ref "U$2") (pin "AJ2") (pinfunction "1_AJ2") (pintype "bidirectional"))
    )
    (net (code "177") (name "~{MS_DISABLE}") (class "Default")
      (node (ref "IC18") (pin "10") (pinfunction "O_10") (pintype "open_collector"))
      (node (ref "U$2") (pin "CV1") (pinfunction "1_CV1") (pintype "bidirectional"))
    )
    (net (code "178") (name "~{RUN}") (class "Default")
      (node (ref "IC10") (pin "2") (pinfunction "I1_2") (pintype "input"))
      (node (ref "IC13") (pin "2") (pinfunction "O_2") (pintype "output"))
      (node (ref "IC13") (pin "4") (pinfunction "I0_4") (pintype "input"))
      (node (ref "IC13") (pin "5") (pinfunction "I1_5") (pintype "input"))
    )
    (net (code "179") (name "~{STOP}") (class "Default")
      (node (ref "IC2") (pin "13") (pinfunction "O_13") (pintype "open_collector"))
      (node (ref "U$2") (pin "DS2") (pinfunction "1_DS2") (pintype "bidirectional"))
    )
    (net (code "180") (name "~{TIMER1}") (class "Default")
      (node (ref "IC25") (pin "10") (pinfunction "I1_10") (pintype "input"))
      (node (ref "IC25") (pin "9") (pinfunction "I0_9") (pintype "input"))
      (node (ref "IC29") (pin "6") (pinfunction "~{Q}_6") (pintype "output"))
    )
    (net (code "181") (name "~{TS4}") (class "Default")
      (node (ref "IC13") (pin "11") (pinfunction "I0_11") (pintype "input"))
      (node (ref "U$2") (pin "CP2") (pinfunction "1_CP2") (pintype "bidirectional"))
    )
  )
)
